# MCU.net
KiCad netlist of a schematic drawn in Altium Designer
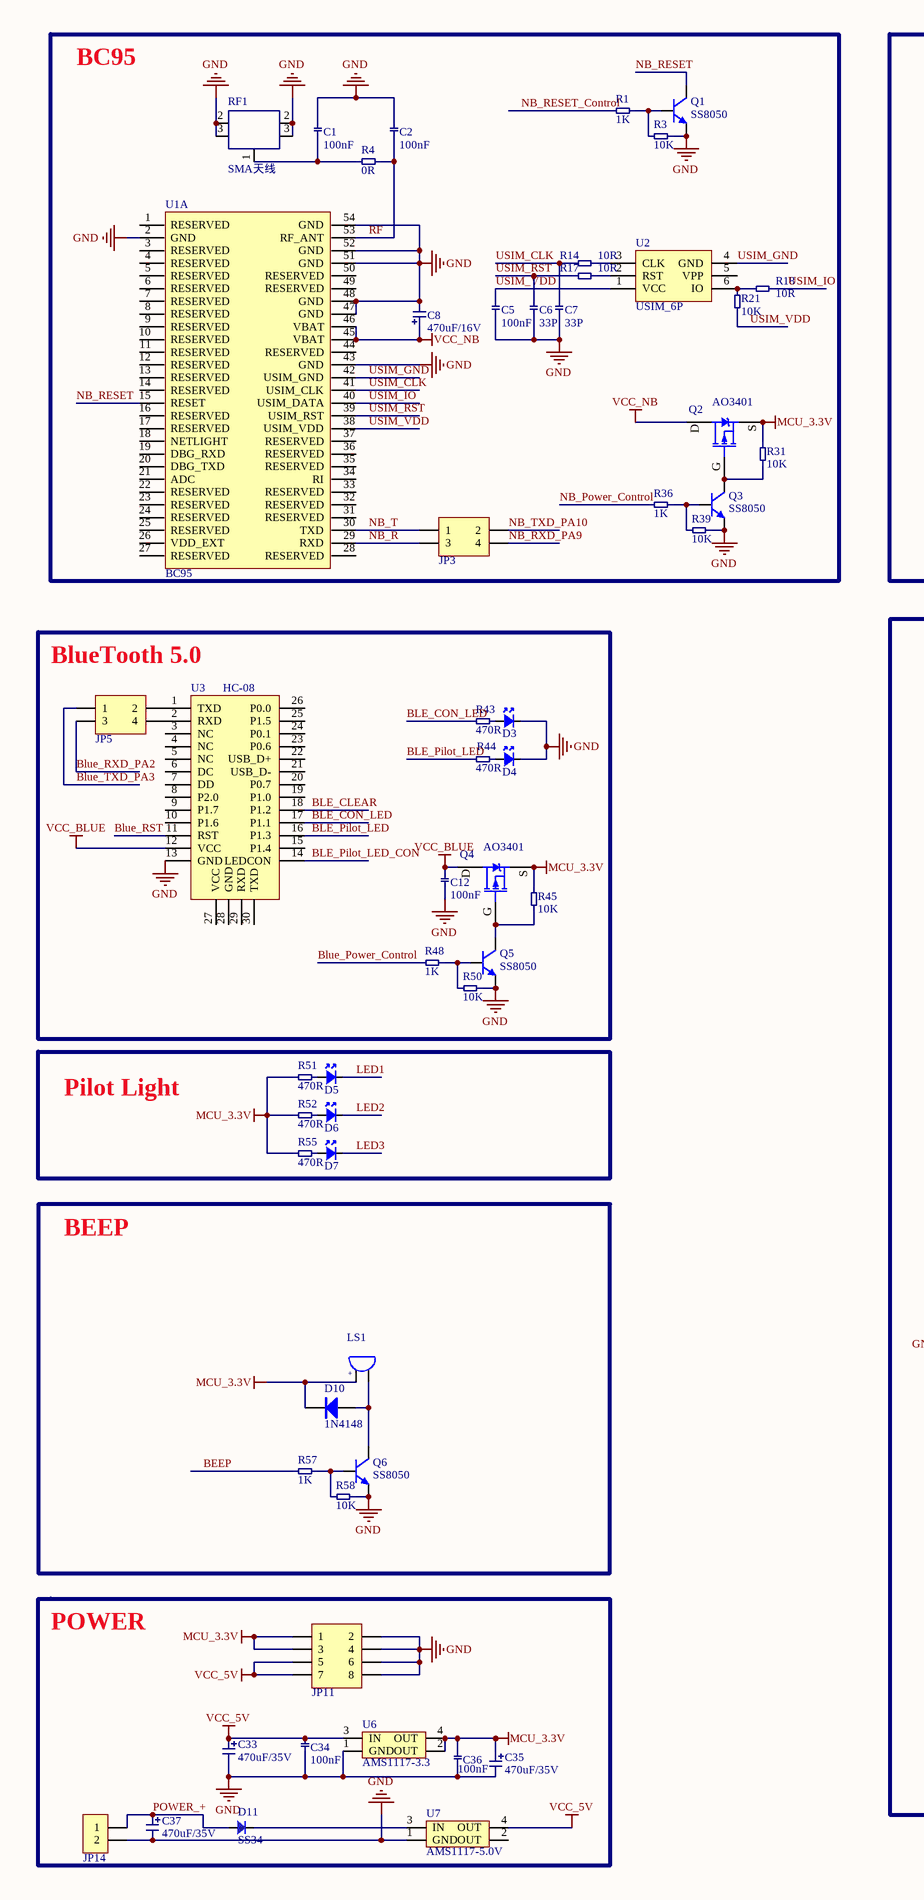
[diagram p0: MCU.SchDoc, left]
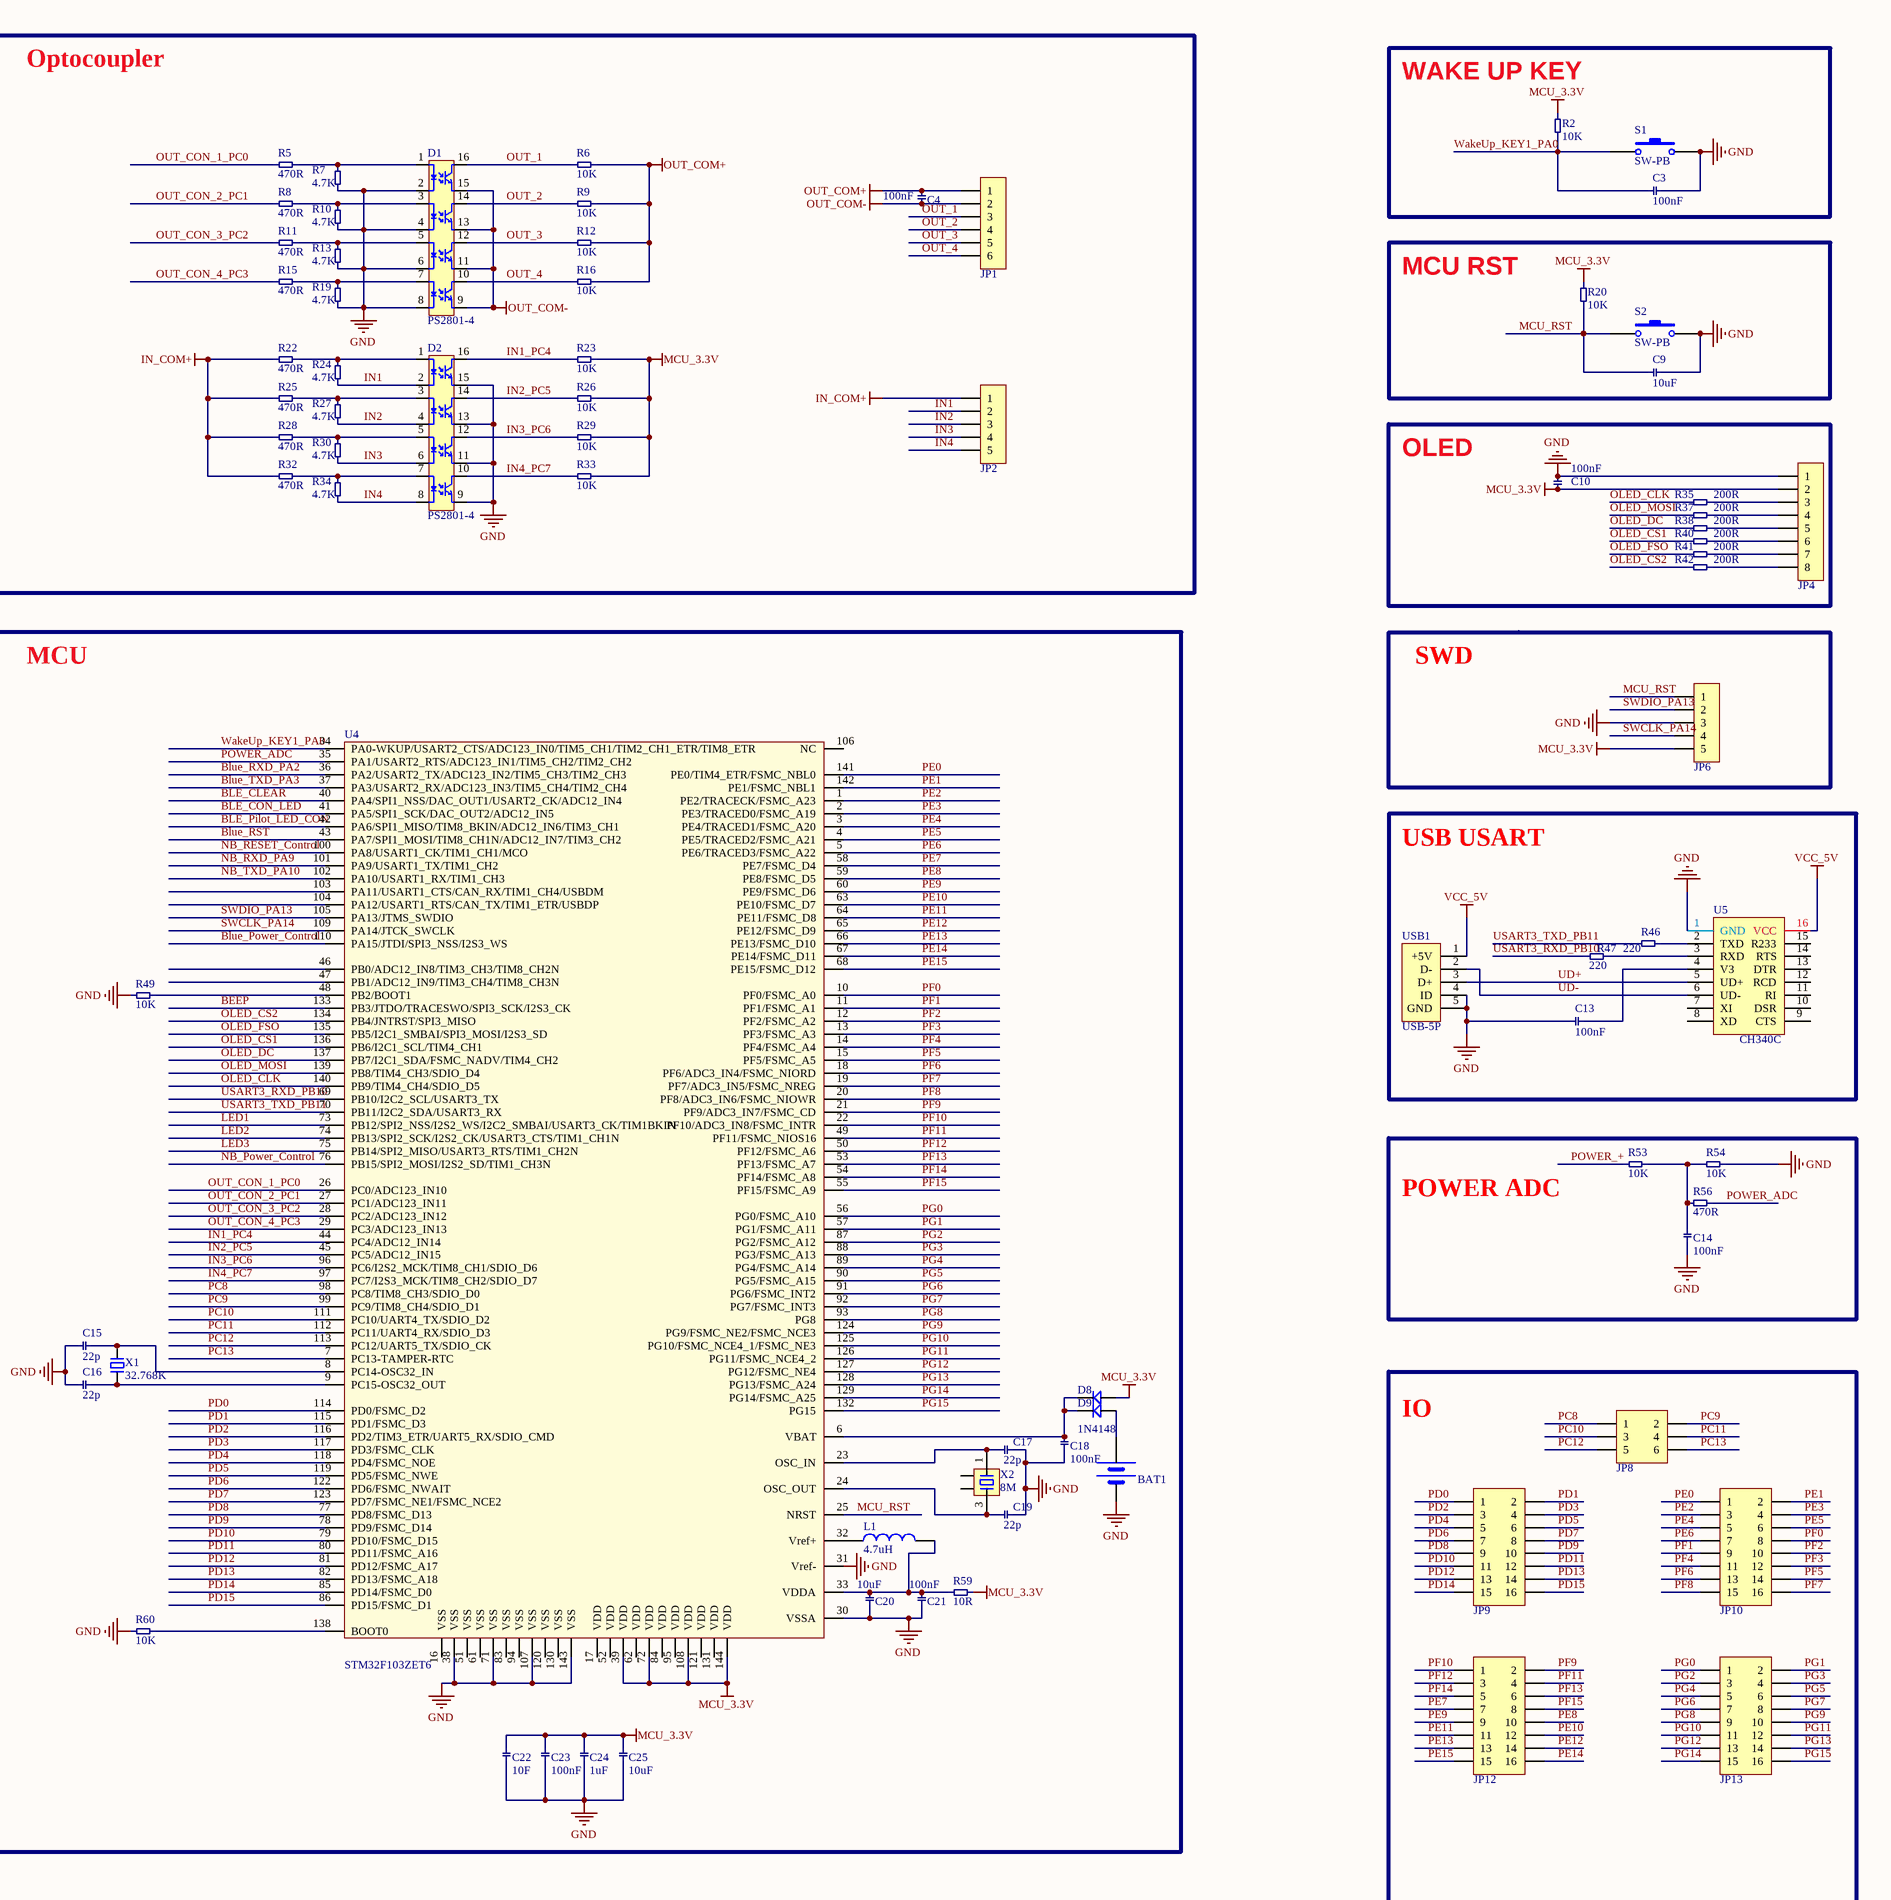
[diagram p1: MCU.SchDoc, right]

(export (version "E")
  (design (tool "Eeschema 10.0.6"))
  (components
    (comp (ref "BAT1")
      (value "BATT")
      (footprint "VBAT")
      (libsource (lib "WarShip V3 STM32103封装库") (part "BAT"))
    )
    (comp (ref "C1") (value "100nF") (footprint "0603CC") (libsource (lib "LFZ@WLP") (part "cap")))
    (comp (ref "C2") (value "100nF") (footprint "0603CC") (libsource (lib "LFZ@WLP") (part "cap")))
    (comp (ref "C3") (value "100nF") (footprint "0603CC") (libsource (lib "LFZ@WLP") (part "cap")))
    (comp (ref "C4") (value "100nF") (footprint "0603CC") (libsource (lib "LFZ@WLP") (part "cap")))
    (comp (ref "C5") (value "100nF") (footprint "0603CC") (libsource (lib "LFZ@WLP") (part "cap")))
    (comp (ref "C6") (value "33P") (footprint "0603CC") (libsource (lib "LFZ@WLP") (part "cap")))
    (comp (ref "C7") (value "33P") (footprint "0603CC") (libsource (lib "LFZ@WLP") (part "cap")))
    (comp (ref "C8") (value "470uF/16V") (footprint "C3216") (libsource (lib "LFZ@WLP") (part "Ecap")))
    (comp (ref "C9") (value "10uF") (footprint "0603CC") (libsource (lib "LFZ@WLP") (part "cap")))
    (comp (ref "C10") (value "100nF") (footprint "0603CC") (libsource (lib "LFZ@WLP") (part "cap")))
    (comp (ref "C12") (value "100nF") (footprint "0603CC") (libsource (lib "LFZ@WLP") (part "cap")))
    (comp (ref "C13") (value "100nF") (footprint "0603CC") (libsource (lib "LFZ@WLP") (part "cap")))
    (comp (ref "C14") (value "100nF") (footprint "0603CC") (libsource (lib "LFZ@WLP") (part "cap")))
    (comp (ref "C15") (value "22p") (footprint "0603CC") (libsource (lib "LFZ@WLP") (part "cap")))
    (comp (ref "C16") (value "22p") (footprint "0603CC") (libsource (lib "LFZ@WLP") (part "cap")))
    (comp (ref "C17") (value "22p") (footprint "0603CC") (libsource (lib "LFZ@WLP") (part "cap")))
    (comp (ref "C18") (value "100nF") (footprint "0603CC") (libsource (lib "LFZ@WLP") (part "cap")))
    (comp (ref "C19") (value "22p") (footprint "0603CC") (libsource (lib "LFZ@WLP") (part "cap")))
    (comp (ref "C20") (value "10uF") (footprint "0603CC") (libsource (lib "LFZ@WLP") (part "cap")))
    (comp (ref "C21") (value "100nF") (footprint "0603CC") (libsource (lib "LFZ@WLP") (part "cap")))
    (comp (ref "C22") (value "10F") (footprint "0603CC") (libsource (lib "LFZ@WLP") (part "cap")))
    (comp (ref "C23") (value "100nF") (footprint "0603CC") (libsource (lib "LFZ@WLP") (part "cap")))
    (comp (ref "C24") (value "1uF") (footprint "0603CC") (libsource (lib "LFZ@WLP") (part "cap")))
    (comp (ref "C25") (value "10uF") (footprint "0603CC") (libsource (lib "LFZ@WLP") (part "cap")))
    (comp (ref "C33") (value "470uF/35V") (footprint "CD A(3216)") (libsource (lib "LFZ@WLP") (part "Ecap")))
    (comp (ref "C34") (value "100nF") (footprint "0603CC") (libsource (lib "LFZ@WLP") (part "cap")))
    (comp (ref "C35") (value "470uF/35V") (footprint "C3216") (libsource (lib "LFZ@WLP") (part "Ecap")))
    (comp (ref "C36") (value "100nF") (footprint "0603CC") (libsource (lib "LFZ@WLP") (part "cap")))
    (comp (ref "C37") (value "470uF/35V") (footprint "CD A(3216)") (libsource (lib "LFZ@WLP") (part "Ecap")))
    (comp (ref "D1") (value "PS2801-4") (footprint "SOP16_N") (libsource (lib "LFZ@WLP") (part "PC847")))
    (comp (ref "D2") (value "PS2801-4") (footprint "SOP16_N") (libsource (lib "LFZ@WLP") (part "PC847")))
    (comp (ref "D3") (value "LED") (footprint "LED 0603G") (libsource (lib "LFZ@WLP") (part "LED")))
    (comp (ref "D4") (value "LED") (footprint "LED 0603R") (libsource (lib "LFZ@WLP") (part "LED")))
    (comp (ref "D5") (value "LED") (footprint "LED 3MM-G") (libsource (lib "LFZ@WLP") (part "LED")))
    (comp (ref "D6") (value "LED") (footprint "LED 3MM-B") (libsource (lib "LFZ@WLP") (part "LED")))
    (comp (ref "D7") (value "LED") (footprint "LED 3MM-R") (libsource (lib "LFZ@WLP") (part "LED")))
    (comp (ref "D8")
      (value "1N4148")
      (footprint "SOD-323")
      (libsource (lib "WarShip V3 STM32103封装库") (part "D"))
    )
    (comp (ref "D9")
      (value "1N4148")
      (footprint "SOD-323")
      (libsource (lib "WarShip V3 STM32103封装库") (part "D"))
    )
    (comp (ref "D10")
      (value "1N4148")
      (footprint "SOD-323")
      (description "高速开关二极管")
      (fields (field (name "版权归属") "源创客"))
      (libsource (lib "8.1   - 二极管-整流桥") (part "1N4148"))
    )
    (comp (ref "D11") (value "SS34") (footprint "SMA") (libsource (lib "Diod") (part "Diod")))
    (comp (ref "JP1")
      (value "HDR-1X6")
      (footprint "XH2.54-LI-6P")
      (description "6P接插件")
      (fields (field (name "版权归属") "源创客"))
      (libsource (lib "4.5   - 接插件-脚距2.54") (part "Header 6"))
    )
    (comp (ref "JP2")
      (value "HDR-1X5")
      (footprint "XH2.54-LI-5P")
      (description "5P接插件")
      (fields (field (name "版权归属") "源创客"))
      (libsource (lib "4.5   - 接插件-脚距2.54") (part "Header 5"))
    )
    (comp (ref "JP3")
      (value "Header2X2")
      (footprint "HDR2.54-LI-2x2P")
      (description "2*2P接插件")
      (fields (field (name "版权归属") "源创客"))
      (libsource (lib "4.5   - 接插件-脚距2.54") (part "Header 2X2"))
    )
    (comp (ref "JP4")
      (value "HDR-1X8")
      (footprint "HDR2.54-M-LI-8P")
      (description "8P接插件")
      (fields (field (name "版权归属") "源创客"))
      (libsource (lib "4.5   - 接插件-脚距2.54") (part "Header 8"))
    )
    (comp (ref "JP5")
      (value "Header2X2")
      (footprint "HDR2.54-LI-2x2P")
      (description "2*2P接插件")
      (fields (field (name "版权归属") "源创客"))
      (libsource (lib "4.5   - 接插件-脚距2.54") (part "Header 2X2"))
    )
    (comp (ref "JP6")
      (value "HDR-1X5")
      (footprint "HDR2.54-LI-5P")
      (description "5P接插件")
      (fields (field (name "版权归属") "源创客"))
      (libsource (lib "4.5   - 接插件-脚距2.54") (part "Header 5"))
    )
    (comp (ref "JP8")
      (value "Header3X2")
      (footprint "HDR2.54-LI-2x3P")
      (description "3*2P接插件")
      (fields (field (name "版权归属") "源创客"))
      (libsource (lib "4.5   - 接插件-脚距2.54") (part "Header 3X2"))
    )
    (comp (ref "JP9")
      (value "Header 8X2")
      (footprint "HDR2.54-LI-2x8P")
      (description "8*2P接插件")
      (fields (field (name "版权归属") "源创客"))
      (libsource (lib "4.5   - 接插件-脚距2.54") (part "Header 8X2"))
    )
    (comp (ref "JP10")
      (value "Header 8X2")
      (footprint "HDR2.54-LI-2x8P")
      (description "8*2P接插件")
      (fields (field (name "版权归属") "源创客"))
      (libsource (lib "4.5   - 接插件-脚距2.54") (part "Header 8X2"))
    )
    (comp (ref "JP11")
      (value "Header 4X2")
      (footprint "HDR2.54-LI-2x4P")
      (description "4*2P接插件")
      (fields (field (name "版权归属") "源创客"))
      (libsource (lib "4.5   - 接插件-脚距2.54") (part "Header 4X2"))
    )
    (comp (ref "JP12")
      (value "Header 8X2")
      (footprint "HDR2.54-LI-2x8P")
      (description "8*2P接插件")
      (fields (field (name "版权归属") "源创客"))
      (libsource (lib "4.5   - 接插件-脚距2.54") (part "Header 8X2"))
    )
    (comp (ref "JP13")
      (value "Header 8X2")
      (footprint "HDR2.54-LI-2x8P")
      (description "8*2P接插件")
      (fields (field (name "版权归属") "源创客"))
      (libsource (lib "4.5   - 接插件-脚距2.54") (part "Header 8X2"))
    )
    (comp (ref "JP14")
      (value "HDR-1X2")
      (footprint "XH2.54-LI-2P")
      (description "2P接插件")
      (fields (field (name "版权归属") "源创客"))
      (libsource (lib "4.5   - 接插件-脚距2.54") (part "Header 2"))
    )
    (comp (ref "L1")
      (value "4.7uH")
      (footprint "L 0603")
      (description "小功率贴片电感")
      (fields (field (name "版权归属") "源创客"))
      (libsource (lib "3.1   - 电阻-电容-电感") (part "L"))
    )
    (comp (ref "LS1")
      (value "DC5V")
      (footprint "BEEP 5x9x5.5")
      (description "蜂鸣器")
      (fields (field (name "版权归属") "源创客"))
      (libsource (lib "15.1 - 未分类器件") (part "BEEP"))
    )
    (comp (ref "Q1")
      (value "SS8050")
      (footprint "SOT23-3N")
      (description "高频放大-NPN型")
      (fields (field (name "版权归属") "源创客"))
      (libsource (lib "6.2   - 三极管") (part "8050-SMD"))
    )
    (comp (ref "Q2")
      (value "AO3401")
      (footprint "SOT23-3N")
      (description "P沟道场效应管")
      (fields (field (name "版权归属") "源创客"))
      (libsource (lib "6.1   - 场效应管-可控硅") (part "SI2301"))
    )
    (comp (ref "Q3")
      (value "SS8050")
      (footprint "SOT23-3N")
      (description "高频放大-NPN型")
      (fields (field (name "版权归属") "源创客"))
      (libsource (lib "6.2   - 三极管") (part "8050-SMD"))
    )
    (comp (ref "Q4")
      (value "AO3401")
      (footprint "SOT23-3N")
      (description "P沟道场效应管")
      (fields (field (name "版权归属") "源创客"))
      (libsource (lib "6.1   - 场效应管-可控硅") (part "SI2301"))
    )
    (comp (ref "Q5")
      (value "SS8050")
      (footprint "SOT23-3N")
      (description "高频放大-NPN型")
      (fields (field (name "版权归属") "源创客"))
      (libsource (lib "6.2   - 三极管") (part "8050-SMD"))
    )
    (comp (ref "Q6")
      (value "SS8050")
      (footprint "SOT23-3N")
      (description "高频放大-NPN型")
      (fields (field (name "版权归属") "源创客"))
      (libsource (lib "6.2   - 三极管") (part "8050-SMD"))
    )
    (comp (ref "R1") (value "1K") (footprint "0603RR") (libsource (lib "LFZ@WLP") (part "res")))
    (comp (ref "R2") (value "10K") (footprint "0603RR") (libsource (lib "LFZ@WLP") (part "res")))
    (comp (ref "R3") (value "10K") (footprint "0603RR") (libsource (lib "LFZ@WLP") (part "res")))
    (comp (ref "R4") (value "0R") (footprint "0603RR") (libsource (lib "LFZ@WLP") (part "res")))
    (comp (ref "R5") (value "470R") (footprint "0603RR") (libsource (lib "LFZ@WLP") (part "res")))
    (comp (ref "R6") (value "10K") (footprint "0603RR") (libsource (lib "LFZ@WLP") (part "res")))
    (comp (ref "R7") (value "4.7K") (footprint "0603RR") (libsource (lib "LFZ@WLP") (part "res")))
    (comp (ref "R8") (value "470R") (footprint "0603RR") (libsource (lib "LFZ@WLP") (part "res")))
    (comp (ref "R9") (value "10K") (footprint "0603RR") (libsource (lib "LFZ@WLP") (part "res")))
    (comp (ref "R10") (value "4.7K") (footprint "0603RR") (libsource (lib "LFZ@WLP") (part "res")))
    (comp (ref "R11") (value "470R") (footprint "0603RR") (libsource (lib "LFZ@WLP") (part "res")))
    (comp (ref "R12") (value "10K") (footprint "0603RR") (libsource (lib "LFZ@WLP") (part "res")))
    (comp (ref "R13") (value "4.7K") (footprint "0603RR") (libsource (lib "LFZ@WLP") (part "res")))
    (comp (ref "R14") (value "10R") (footprint "0603RR") (libsource (lib "LFZ@WLP") (part "res")))
    (comp (ref "R15") (value "470R") (footprint "0603RR") (libsource (lib "LFZ@WLP") (part "res")))
    (comp (ref "R16") (value "10K") (footprint "0603RR") (libsource (lib "LFZ@WLP") (part "res")))
    (comp (ref "R17") (value "10R") (footprint "0603RR") (libsource (lib "LFZ@WLP") (part "res")))
    (comp (ref "R18") (value "10R") (footprint "0603RR") (libsource (lib "LFZ@WLP") (part "res")))
    (comp (ref "R19") (value "4.7K") (footprint "0603RR") (libsource (lib "LFZ@WLP") (part "res")))
    (comp (ref "R20") (value "10K") (footprint "0603RR") (libsource (lib "LFZ@WLP") (part "res")))
    (comp (ref "R21") (value "10K") (footprint "0603RR") (libsource (lib "LFZ@WLP") (part "res")))
    (comp (ref "R22") (value "470R") (footprint "0603RR") (libsource (lib "LFZ@WLP") (part "res")))
    (comp (ref "R23") (value "10K") (footprint "0603RR") (libsource (lib "LFZ@WLP") (part "res")))
    (comp (ref "R24") (value "4.7K") (footprint "0603RR") (libsource (lib "LFZ@WLP") (part "res")))
    (comp (ref "R25") (value "470R") (footprint "0603RR") (libsource (lib "LFZ@WLP") (part "res")))
    (comp (ref "R26") (value "10K") (footprint "0603RR") (libsource (lib "LFZ@WLP") (part "res")))
    (comp (ref "R27") (value "4.7K") (footprint "0603RR") (libsource (lib "LFZ@WLP") (part "res")))
    (comp (ref "R28") (value "470R") (footprint "0603RR") (libsource (lib "LFZ@WLP") (part "res")))
    (comp (ref "R29") (value "10K") (footprint "0603RR") (libsource (lib "LFZ@WLP") (part "res")))
    (comp (ref "R30") (value "4.7K") (footprint "0603RR") (libsource (lib "LFZ@WLP") (part "res")))
    (comp (ref "R31") (value "10K") (footprint "0603RR") (libsource (lib "LFZ@WLP") (part "res")))
    (comp (ref "R32") (value "470R") (footprint "0603RR") (libsource (lib "LFZ@WLP") (part "res")))
    (comp (ref "R33") (value "10K") (footprint "0603RR") (libsource (lib "LFZ@WLP") (part "res")))
    (comp (ref "R34") (value "4.7K") (footprint "0603RR") (libsource (lib "LFZ@WLP") (part "res")))
    (comp (ref "R35") (value "200R") (footprint "0603RR") (libsource (lib "LFZ@WLP") (part "res")))
    (comp (ref "R36") (value "1K") (footprint "0603RR") (libsource (lib "LFZ@WLP") (part "res")))
    (comp (ref "R37") (value "200R") (footprint "0603RR") (libsource (lib "LFZ@WLP") (part "res")))
    (comp (ref "R38") (value "200R") (footprint "0603RR") (libsource (lib "LFZ@WLP") (part "res")))
    (comp (ref "R39") (value "10K") (footprint "0603RR") (libsource (lib "LFZ@WLP") (part "res")))
    (comp (ref "R40") (value "200R") (footprint "0603RR") (libsource (lib "LFZ@WLP") (part "res")))
    (comp (ref "R41") (value "200R") (footprint "0603RR") (libsource (lib "LFZ@WLP") (part "res")))
    (comp (ref "R42") (value "200R") (footprint "0603RR") (libsource (lib "LFZ@WLP") (part "res")))
    (comp (ref "R43") (value "470R") (footprint "0603RR") (libsource (lib "LFZ@WLP") (part "res")))
    (comp (ref "R44") (value "470R") (footprint "0603RR") (libsource (lib "LFZ@WLP") (part "res")))
    (comp (ref "R45") (value "10K") (footprint "0603RR") (libsource (lib "LFZ@WLP") (part "res")))
    (comp (ref "R46") (value "220") (footprint "0603RR") (libsource (lib "LFZ@WLP") (part "res")))
    (comp (ref "R47") (value "220") (footprint "0603RR") (libsource (lib "LFZ@WLP") (part "res")))
    (comp (ref "R48") (value "1K") (footprint "0603RR") (libsource (lib "LFZ@WLP") (part "res")))
    (comp (ref "R49") (value "10K") (footprint "0603RR") (libsource (lib "LFZ@WLP") (part "res")))
    (comp (ref "R50") (value "10K") (footprint "0603RR") (libsource (lib "LFZ@WLP") (part "res")))
    (comp (ref "R51") (value "470R") (footprint "0603RR") (libsource (lib "LFZ@WLP") (part "res")))
    (comp (ref "R52") (value "470R") (footprint "0603RR") (libsource (lib "LFZ@WLP") (part "res")))
    (comp (ref "R53") (value "10K") (footprint "0603RR") (libsource (lib "LFZ@WLP") (part "res")))
    (comp (ref "R54") (value "10K") (footprint "0603RR") (libsource (lib "LFZ@WLP") (part "res")))
    (comp (ref "R55") (value "470R") (footprint "0603RR") (libsource (lib "LFZ@WLP") (part "res")))
    (comp (ref "R56") (value "470R") (footprint "0603RR") (libsource (lib "LFZ@WLP") (part "res")))
    (comp (ref "R57") (value "1K") (footprint "0603RR") (libsource (lib "LFZ@WLP") (part "res")))
    (comp (ref "R58") (value "10K") (footprint "0603RR") (libsource (lib "LFZ@WLP") (part "res")))
    (comp (ref "R59") (value "10R") (footprint "0603RR") (libsource (lib "LFZ@WLP") (part "res")))
    (comp (ref "R60") (value "10K") (footprint "0603RR") (libsource (lib "LFZ@WLP") (part "res")))
    (comp (ref "RF1") (value "SMA天线") (libsource (lib "LFZ@WLP") (part "SMA天线")))
    (comp (ref "S1")
      (value "SW-PB")
      (footprint "TSW SMD-6*6*6")
      (description "Switch")
      (fields (field (name "PUBLISHER") "Altium Limited"))
      (libsource (lib "开关及电源") (part "SW-PB"))
    )
    (comp (ref "S2")
      (value "SW-PB")
      (footprint "TSW SMD-4*4*1.5")
      (description "Switch")
      (fields (field (name "PUBLISHER") "Altium Limited"))
      (libsource (lib "开关及电源") (part "SW-PB"))
    )
    (comp (ref "U1")
      (value "BC95")
      (footprint "BC95")
      (libsource (lib "Quectel_BC95_SCH_Part_Protel&AD_20170925") (part "BC95"))
    )
    (comp (ref "U2") (value "USIM_6P") (footprint "SIM 6P 自弹") (libsource (lib "XG-BM02") (part "USIM-6P")))
    (comp (ref "U3") (value "HC-08") (footprint "HC-08") (libsource (lib "LFZ@WLP") (part "HC-08")))
    (comp (ref "U4")
      (value "STM32F103ZET6")
      (footprint "LQFP144 20X20_L")
      (libsource (lib "WarShip V3 STM32103封装库") (part "STM32F103ZET6"))
    )
    (comp (ref "U5") (value "CH340C") (footprint "SOP16_L") (libsource (lib "LFZ@WLP") (part "CH340C")))
    (comp (ref "U6")
      (value "AMS1117-3.3")
      (footprint "SOT223_N")
      (libsource (lib "WarShip V3 STM32103封装库") (part "AMS1117"))
    )
    (comp (ref "U7")
      (value "AMS1117-5.0V")
      (footprint "SOT223_N")
      (libsource (lib "WarShip V3 STM32103封装库") (part "AMS1117"))
    )
    (comp (ref "USB1")
      (value "USB-5P")
      (footprint "USB-MICRO_A")
      (description "微型USB母座")
      (fields (field (name "版权归属") "源创客"))
      (libsource (lib "4.1   - 接口类") (part "USB-5P"))
    )
    (comp (ref "X1")
      (value "32.768K")
      (footprint "OSC 3215-2P")
      (description "2脚无源脚晶振")
      (fields (field (name "版权归属") "源创客"))
      (libsource (lib "10.1 - 保险丝-晶振") (part "XTAL-2P"))
    )
    (comp (ref "X2")
      (value "8M")
      (footprint "OSC 3225-4P")
      (description "4脚无源晶振")
      (fields (field (name "版权归属") "源创客"))
      (libsource (lib "10.1 - 保险丝-晶振") (part "XTAL-4P"))
    )
  )
  (nets
    (net (code "1") (name "/BEEP") (class "Default")
      (node (ref "R57") (pin "1") (pinfunction "1_1") (pintype "passive"))
      (node (ref "U4") (pin "133") (pinfunction "PB3/JTDO/TRACESWO/SPI3_SCK/I2S3_CK_133") (pintype "passive"))
    )
    (net (code "2") (name "/BLE_CLEAR") (class "Default")
      (node (ref "U3") (pin "18") (pinfunction "P1.2_18") (pintype "passive"))
      (node (ref "U4") (pin "40") (pinfunction "PA4/SPI1_NSS/DAC_OUT1/USART2_CK/ADC12_IN4_40") (pintype "passive"))
    )
    (net (code "3") (name "/BLE_CON_LED") (class "Default")
      (node (ref "R43") (pin "1") (pinfunction "1_1") (pintype "passive"))
      (node (ref "U3") (pin "17") (pinfunction "P1.1_17") (pintype "passive"))
      (node (ref "U4") (pin "41") (pinfunction "PA5/SPI1_SCK/DAC_OUT2/ADC12_IN5_41") (pintype "passive"))
    )
    (net (code "4") (name "/BLE_Pilot_LED") (class "Default")
      (node (ref "R44") (pin "1") (pinfunction "1_1") (pintype "passive"))
      (node (ref "U3") (pin "16") (pinfunction "P1.3_16") (pintype "passive"))
    )
    (net (code "5") (name "/BLE_Pilot_LED_CON") (class "Default")
      (node (ref "U3") (pin "14") (pinfunction "LEDCON_14") (pintype "passive"))
      (node (ref "U4") (pin "42") (pinfunction "PA6/SPI1_MISO/TIM8_BKIN/ADC12_IN6/TIM3_CH1_42") (pintype "passive"))
    )
    (net (code "6") (name "/Blue_Power_Control") (class "Default")
      (node (ref "R48") (pin "1") (pinfunction "1_1") (pintype "passive"))
      (node (ref "U4") (pin "110") (pinfunction "PA15/JTDI/SPI3_NSS/I2S3_WS_110") (pintype "passive"))
    )
    (net (code "7") (name "/Blue_RST") (class "Default")
      (node (ref "U3") (pin "11") (pinfunction "RST_11") (pintype "passive"))
      (node (ref "U4") (pin "43") (pinfunction "PA7/SPI1_MOSI/TIM8_CH1N/ADC12_IN7/TIM3_CH2_43") (pintype "passive"))
    )
    (net (code "8") (name "/Blue_RXD_PA2") (class "Default")
      (node (ref "JP5") (pin "3") (pinfunction "3_3") (pintype "passive"))
      (node (ref "U4") (pin "36") (pinfunction "PA2/USART2_TX/ADC123_IN2/TIM5_CH3/TIM2_CH3_36") (pintype "passive"))
    )
    (net (code "9") (name "/Blue_TXD_PA3") (class "Default")
      (node (ref "JP5") (pin "1") (pinfunction "1_1") (pintype "passive"))
      (node (ref "U4") (pin "37") (pinfunction "PA3/USART2_RX/ADC123_IN3/TIM5_CH4/TIM2_CH4_37") (pintype "passive"))
    )
    (net (code "10") (name "/IN1") (class "Default")
      (node (ref "D2") (pin "2") (pinfunction "IN_N_2") (pintype "passive"))
      (node (ref "JP2") (pin "2") (pinfunction "2_2") (pintype "passive"))
      (node (ref "R24") (pin "1") (pinfunction "1_1") (pintype "passive"))
    )
    (net (code "11") (name "/IN1_PC4") (class "Default")
      (node (ref "D2") (pin "16") (pinfunction "OUT_C_16") (pintype "passive"))
      (node (ref "R23") (pin "1") (pinfunction "1_1") (pintype "passive"))
      (node (ref "U4") (pin "44") (pinfunction "PC4/ADC12_IN14_44") (pintype "passive"))
    )
    (net (code "12") (name "/IN2") (class "Default")
      (node (ref "D2") (pin "4") (pinfunction "IN_N_4") (pintype "passive"))
      (node (ref "JP2") (pin "3") (pinfunction "3_3") (pintype "passive"))
      (node (ref "R27") (pin "1") (pinfunction "1_1") (pintype "passive"))
    )
    (net (code "13") (name "/IN2_PC5") (class "Default")
      (node (ref "D2") (pin "14") (pinfunction "OUT_C_14") (pintype "passive"))
      (node (ref "R26") (pin "1") (pinfunction "1_1") (pintype "passive"))
      (node (ref "U4") (pin "45") (pinfunction "PC5/ADC12_IN15_45") (pintype "passive"))
    )
    (net (code "14") (name "/IN3") (class "Default")
      (node (ref "D2") (pin "6") (pinfunction "IN_N_6") (pintype "passive"))
      (node (ref "JP2") (pin "4") (pinfunction "4_4") (pintype "passive"))
      (node (ref "R30") (pin "1") (pinfunction "1_1") (pintype "passive"))
    )
    (net (code "15") (name "/IN3_PC6") (class "Default")
      (node (ref "D2") (pin "12") (pinfunction "OUT_C_12") (pintype "passive"))
      (node (ref "R29") (pin "1") (pinfunction "1_1") (pintype "passive"))
      (node (ref "U4") (pin "96") (pinfunction "PC6/I2S2_MCK/TIM8_CH1/SDIO_D6_96") (pintype "passive"))
    )
    (net (code "16") (name "/IN4") (class "Default")
      (node (ref "D2") (pin "8") (pinfunction "IN_N_8") (pintype "passive"))
      (node (ref "JP2") (pin "5") (pinfunction "5_5") (pintype "passive"))
      (node (ref "R34") (pin "1") (pinfunction "1_1") (pintype "passive"))
    )
    (net (code "17") (name "/IN4_PC7") (class "Default")
      (node (ref "D2") (pin "10") (pinfunction "OUT_C_10") (pintype "passive"))
      (node (ref "R33") (pin "1") (pinfunction "1_1") (pintype "passive"))
      (node (ref "U4") (pin "97") (pinfunction "PC7/I2S3_MCK/TIM8_CH2/SDIO_D7_97") (pintype "passive"))
    )
    (net (code "18") (name "/LED1") (class "Default")
      (node (ref "D5") (pin "2") (pinfunction "CATHODE_2") (pintype "passive"))
      (node (ref "U4") (pin "73") (pinfunction "PB12/SPI2_NSS/I2S2_WS/I2C2_SMBAI/USART3_CK/TIM1BKIN_73") (pintype "passive"))
    )
    (net (code "19") (name "/LED2") (class "Default")
      (node (ref "D6") (pin "2") (pinfunction "CATHODE_2") (pintype "passive"))
      (node (ref "U4") (pin "74") (pinfunction "PB13/SPI2_SCK/I2S2_CK/USART3_CTS/TIM1_CH1N_74") (pintype "passive"))
    )
    (net (code "20") (name "/LED3") (class "Default")
      (node (ref "D7") (pin "2") (pinfunction "CATHODE_2") (pintype "passive"))
      (node (ref "U4") (pin "75") (pinfunction "PB14/SPI2_MISO/USART3_RTS/TIM1_CH2N_75") (pintype "passive"))
    )
    (net (code "21") (name "/MCU_RST") (class "Default")
      (node (ref "C9") (pin "2") (pinfunction "2_2") (pintype "passive"))
      (node (ref "JP6") (pin "1") (pinfunction "1_1") (pintype "passive"))
      (node (ref "R20") (pin "1") (pinfunction "1_1") (pintype "passive"))
      (node (ref "S2") (pin "1") (pinfunction "1_1") (pintype "passive"))
      (node (ref "U4") (pin "25") (pinfunction "NRST_25") (pintype "passive"))
    )
    (net (code "22") (name "/NB_Power_Control") (class "Default")
      (node (ref "R36") (pin "1") (pinfunction "1_1") (pintype "passive"))
      (node (ref "U4") (pin "76") (pinfunction "PB15/SPI2_MOSI/I2S2_SD/TIM1_CH3N_76") (pintype "passive"))
    )
    (net (code "23") (name "/NB_R") (class "Default")
      (node (ref "JP3") (pin "3") (pinfunction "3_3") (pintype "passive"))
      (node (ref "U1") (pin "29") (pinfunction "RXD_29") (pintype "passive"))
    )
    (net (code "24") (name "/NB_RESET") (class "Default")
      (node (ref "Q1") (pin "3") (pinfunction "C_3") (pintype "passive"))
      (node (ref "U1") (pin "15") (pinfunction "RESET_15") (pintype "passive"))
    )
    (net (code "25") (name "/NB_RESET_Control") (class "Default")
      (node (ref "R1") (pin "1") (pinfunction "1_1") (pintype "passive"))
      (node (ref "U4") (pin "100") (pinfunction "PA8/USART1_CK/TIM1_CH1/MCO_100") (pintype "passive"))
    )
    (net (code "26") (name "/NB_RXD_PA9") (class "Default")
      (node (ref "JP3") (pin "4") (pinfunction "4_4") (pintype "passive"))
      (node (ref "U4") (pin "101") (pinfunction "PA9/USART1_TX/TIM1_CH2_101") (pintype "passive"))
    )
    (net (code "27") (name "/NB_T") (class "Default")
      (node (ref "JP3") (pin "1") (pinfunction "1_1") (pintype "passive"))
      (node (ref "U1") (pin "30") (pinfunction "TXD_30") (pintype "passive"))
    )
    (net (code "28") (name "/NB_TXD_PA10") (class "Default")
      (node (ref "JP3") (pin "2") (pinfunction "2_2") (pintype "passive"))
      (node (ref "U4") (pin "102") (pinfunction "PA10/USART1_RX/TIM1_CH3_102") (pintype "passive"))
    )
    (net (code "29") (name "/OLED_CLK") (class "Default")
      (node (ref "R35") (pin "1") (pinfunction "1_1") (pintype "passive"))
      (node (ref "U4") (pin "140") (pinfunction "PB9/TIM4_CH4/SDIO_D5_140") (pintype "passive"))
    )
    (net (code "30") (name "/OLED_CS1") (class "Default")
      (node (ref "R40") (pin "1") (pinfunction "1_1") (pintype "passive"))
      (node (ref "U4") (pin "136") (pinfunction "PB6/I2C1_SCL/TIM4_CH1_136") (pintype "passive"))
    )
    (net (code "31") (name "/OLED_CS2") (class "Default")
      (node (ref "R42") (pin "1") (pinfunction "1_1") (pintype "passive"))
      (node (ref "U4") (pin "134") (pinfunction "PB4/JNTRST/SPI3_MISO_134") (pintype "passive"))
    )
    (net (code "32") (name "/OLED_DC") (class "Default")
      (node (ref "R38") (pin "1") (pinfunction "1_1") (pintype "passive"))
      (node (ref "U4") (pin "137") (pinfunction "PB7/I2C1_SDA/FSMC_NADV/TIM4_CH2_137") (pintype "passive"))
    )
    (net (code "33") (name "/OLED_FSO") (class "Default")
      (node (ref "R41") (pin "1") (pinfunction "1_1") (pintype "passive"))
      (node (ref "U4") (pin "135") (pinfunction "PB5/I2C1_SMBAI/SPI3_MOSI/I2S3_SD_135") (pintype "passive"))
    )
    (net (code "34") (name "/OLED_MOSI") (class "Default")
      (node (ref "R37") (pin "1") (pinfunction "1_1") (pintype "passive"))
      (node (ref "U4") (pin "139") (pinfunction "PB8/TIM4_CH3/SDIO_D4_139") (pintype "passive"))
    )
    (net (code "35") (name "/OUT_1") (class "Default")
      (node (ref "D1") (pin "16") (pinfunction "OUT_C_16") (pintype "passive"))
      (node (ref "JP1") (pin "3") (pinfunction "3_3") (pintype "passive"))
      (node (ref "R6") (pin "2") (pinfunction "2_2") (pintype "passive"))
    )
    (net (code "36") (name "/OUT_2") (class "Default")
      (node (ref "D1") (pin "14") (pinfunction "OUT_C_14") (pintype "passive"))
      (node (ref "JP1") (pin "4") (pinfunction "4_4") (pintype "passive"))
      (node (ref "R9") (pin "2") (pinfunction "2_2") (pintype "passive"))
    )
    (net (code "37") (name "/OUT_3") (class "Default")
      (node (ref "D1") (pin "12") (pinfunction "OUT_C_12") (pintype "passive"))
      (node (ref "JP1") (pin "5") (pinfunction "5_5") (pintype "passive"))
      (node (ref "R12") (pin "2") (pinfunction "2_2") (pintype "passive"))
    )
    (net (code "38") (name "/OUT_4") (class "Default")
      (node (ref "D1") (pin "10") (pinfunction "OUT_C_10") (pintype "passive"))
      (node (ref "JP1") (pin "6") (pinfunction "6_6") (pintype "passive"))
      (node (ref "R16") (pin "2") (pinfunction "2_2") (pintype "passive"))
    )
    (net (code "39") (name "/OUT_CON_1_PC0") (class "Default")
      (node (ref "R5") (pin "1") (pinfunction "1_1") (pintype "passive"))
      (node (ref "U4") (pin "26") (pinfunction "PC0/ADC123_IN10_26") (pintype "passive"))
    )
    (net (code "40") (name "/OUT_CON_2_PC1") (class "Default")
      (node (ref "R8") (pin "1") (pinfunction "1_1") (pintype "passive"))
      (node (ref "U4") (pin "27") (pinfunction "PC1/ADC123_IN11_27") (pintype "passive"))
    )
    (net (code "41") (name "/OUT_CON_3_PC2") (class "Default")
      (node (ref "R11") (pin "1") (pinfunction "1_1") (pintype "passive"))
      (node (ref "U4") (pin "28") (pinfunction "PC2/ADC123_IN12_28") (pintype "passive"))
    )
    (net (code "42") (name "/OUT_CON_4_PC3") (class "Default")
      (node (ref "R15") (pin "1") (pinfunction "1_1") (pintype "passive"))
      (node (ref "U4") (pin "29") (pinfunction "PC3/ADC123_IN13_29") (pintype "passive"))
    )
    (net (code "43") (name "/PC8") (class "Default")
      (node (ref "JP8") (pin "1") (pinfunction "1_1") (pintype "passive"))
      (node (ref "U4") (pin "98") (pinfunction "PC8/TIM8_CH3/SDIO_D0_98") (pintype "passive"))
    )
    (net (code "44") (name "/PC9") (class "Default")
      (node (ref "JP8") (pin "2") (pinfunction "2_2") (pintype "passive"))
      (node (ref "U4") (pin "99") (pinfunction "PC9/TIM8_CH4/SDIO_D1_99") (pintype "passive"))
    )
    (net (code "45") (name "/PC10") (class "Default")
      (node (ref "JP8") (pin "3") (pinfunction "3_3") (pintype "passive"))
      (node (ref "U4") (pin "111") (pinfunction "PC10/UART4_TX/SDIO_D2_111") (pintype "passive"))
    )
    (net (code "46") (name "/PC11") (class "Default")
      (node (ref "JP8") (pin "4") (pinfunction "4_4") (pintype "passive"))
      (node (ref "U4") (pin "112") (pinfunction "PC11/UART4_RX/SDIO_D3_112") (pintype "passive"))
    )
    (net (code "47") (name "/PC12") (class "Default")
      (node (ref "JP8") (pin "5") (pinfunction "5_5") (pintype "passive"))
      (node (ref "U4") (pin "113") (pinfunction "PC12/UART5_TX/SDIO_CK_113") (pintype "passive"))
    )
    (net (code "48") (name "/PC13") (class "Default")
      (node (ref "JP8") (pin "6") (pinfunction "6_6") (pintype "passive"))
      (node (ref "U4") (pin "7") (pinfunction "PC13-TAMPER-RTC_7") (pintype "passive"))
    )
    (net (code "49") (name "/PD0") (class "Default")
      (node (ref "JP9") (pin "1") (pinfunction "1_1") (pintype "passive"))
      (node (ref "U4") (pin "114") (pinfunction "PD0/FSMC_D2_114") (pintype "passive"))
    )
    (net (code "50") (name "/PD1") (class "Default")
      (node (ref "JP9") (pin "2") (pinfunction "2_2") (pintype "passive"))
      (node (ref "U4") (pin "115") (pinfunction "PD1/FSMC_D3_115") (pintype "passive"))
    )
    (net (code "51") (name "/PD2") (class "Default")
      (node (ref "JP9") (pin "3") (pinfunction "3_3") (pintype "passive"))
      (node (ref "U4") (pin "116") (pinfunction "PD2/TIM3_ETR/UART5_RX/SDIO_CMD_116") (pintype "passive"))
    )
    (net (code "52") (name "/PD3") (class "Default")
      (node (ref "JP9") (pin "4") (pinfunction "4_4") (pintype "passive"))
      (node (ref "U4") (pin "117") (pinfunction "PD3/FSMC_CLK_117") (pintype "passive"))
    )
    (net (code "53") (name "/PD4") (class "Default")
      (node (ref "JP9") (pin "5") (pinfunction "5_5") (pintype "passive"))
      (node (ref "U4") (pin "118") (pinfunction "PD4/FSMC_NOE_118") (pintype "passive"))
    )
    (net (code "54") (name "/PD5") (class "Default")
      (node (ref "JP9") (pin "6") (pinfunction "6_6") (pintype "passive"))
      (node (ref "U4") (pin "119") (pinfunction "PD5/FSMC_NWE_119") (pintype "passive"))
    )
    (net (code "55") (name "/PD6") (class "Default")
      (node (ref "JP9") (pin "7") (pinfunction "7_7") (pintype "passive"))
      (node (ref "U4") (pin "122") (pinfunction "PD6/FSMC_NWAIT_122") (pintype "passive"))
    )
    (net (code "56") (name "/PD7") (class "Default")
      (node (ref "JP9") (pin "8") (pinfunction "8_8") (pintype "passive"))
      (node (ref "U4") (pin "123") (pinfunction "PD7/FSMC_NE1/FSMC_NCE2_123") (pintype "passive"))
    )
    (net (code "57") (name "/PD8") (class "Default")
      (node (ref "JP9") (pin "9") (pinfunction "9_9") (pintype "passive"))
      (node (ref "U4") (pin "77") (pinfunction "PD8/FSMC_D13_77") (pintype "passive"))
    )
    (net (code "58") (name "/PD9") (class "Default")
      (node (ref "JP9") (pin "10") (pinfunction "10_10") (pintype "passive"))
      (node (ref "U4") (pin "78") (pinfunction "PD9/FSMC_D14_78") (pintype "passive"))
    )
    (net (code "59") (name "/PD10") (class "Default")
      (node (ref "JP9") (pin "11") (pinfunction "11_11") (pintype "passive"))
      (node (ref "U4") (pin "79") (pinfunction "PD10/FSMC_D15_79") (pintype "passive"))
    )
    (net (code "60") (name "/PD11") (class "Default")
      (node (ref "JP9") (pin "12") (pinfunction "12_12") (pintype "passive"))
      (node (ref "U4") (pin "80") (pinfunction "PD11/FSMC_A16_80") (pintype "passive"))
    )
    (net (code "61") (name "/PD12") (class "Default")
      (node (ref "JP9") (pin "13") (pinfunction "13_13") (pintype "passive"))
      (node (ref "U4") (pin "81") (pinfunction "PD12/FSMC_A17_81") (pintype "passive"))
    )
    (net (code "62") (name "/PD13") (class "Default")
      (node (ref "JP9") (pin "14") (pinfunction "14_14") (pintype "passive"))
      (node (ref "U4") (pin "82") (pinfunction "PD13/FSMC_A18_82") (pintype "passive"))
    )
    (net (code "63") (name "/PD14") (class "Default")
      (node (ref "JP9") (pin "15") (pinfunction "15_15") (pintype "passive"))
      (node (ref "U4") (pin "85") (pinfunction "PD14/FSMC_D0_85") (pintype "passive"))
    )
    (net (code "64") (name "/PD15") (class "Default")
      (node (ref "JP9") (pin "16") (pinfunction "16_16") (pintype "passive"))
      (node (ref "U4") (pin "86") (pinfunction "PD15/FSMC_D1_86") (pintype "passive"))
    )
    (net (code "65") (name "/PE0") (class "Default")
      (node (ref "JP10") (pin "1") (pinfunction "1_1") (pintype "passive"))
      (node (ref "U4") (pin "141") (pinfunction "PE0/TIM4_ETR/FSMC_NBL0_141") (pintype "passive"))
    )
    (net (code "66") (name "/PE1") (class "Default")
      (node (ref "JP10") (pin "2") (pinfunction "2_2") (pintype "passive"))
      (node (ref "U4") (pin "142") (pinfunction "PE1/FSMC_NBL1_142") (pintype "passive"))
    )
    (net (code "67") (name "/PE2") (class "Default")
      (node (ref "JP10") (pin "3") (pinfunction "3_3") (pintype "passive"))
      (node (ref "U4") (pin "1") (pinfunction "PE2/TRACECK/FSMC_A23_1") (pintype "passive"))
    )
    (net (code "68") (name "/PE3") (class "Default")
      (node (ref "JP10") (pin "4") (pinfunction "4_4") (pintype "passive"))
      (node (ref "U4") (pin "2") (pinfunction "PE3/TRACED0/FSMC_A19_2") (pintype "passive"))
    )
    (net (code "69") (name "/PE4") (class "Default")
      (node (ref "JP10") (pin "5") (pinfunction "5_5") (pintype "passive"))
      (node (ref "U4") (pin "3") (pinfunction "PE4/TRACED1/FSMC_A20_3") (pintype "passive"))
    )
    (net (code "70") (name "/PE5") (class "Default")
      (node (ref "JP10") (pin "6") (pinfunction "6_6") (pintype "passive"))
      (node (ref "U4") (pin "4") (pinfunction "PE5/TRACED2/FSMC_A21_4") (pintype "passive"))
    )
    (net (code "71") (name "/PE6") (class "Default")
      (node (ref "JP10") (pin "7") (pinfunction "7_7") (pintype "passive"))
      (node (ref "U4") (pin "5") (pinfunction "PE6/TRACED3/FSMC_A22_5") (pintype "passive"))
    )
    (net (code "72") (name "/PE7") (class "Default")
      (node (ref "JP12") (pin "7") (pinfunction "7_7") (pintype "passive"))
      (node (ref "U4") (pin "58") (pinfunction "PE7/FSMC_D4_58") (pintype "passive"))
    )
    (net (code "73") (name "/PE8") (class "Default")
      (node (ref "JP12") (pin "10") (pinfunction "10_10") (pintype "passive"))
      (node (ref "U4") (pin "59") (pinfunction "PE8/FSMC_D5_59") (pintype "passive"))
    )
    (net (code "74") (name "/PE9") (class "Default")
      (node (ref "JP12") (pin "9") (pinfunction "9_9") (pintype "passive"))
      (node (ref "U4") (pin "60") (pinfunction "PE9/FSMC_D6_60") (pintype "passive"))
    )
    (net (code "75") (name "/PE10") (class "Default")
      (node (ref "JP12") (pin "12") (pinfunction "12_12") (pintype "passive"))
      (node (ref "U4") (pin "63") (pinfunction "PE10/FSMC_D7_63") (pintype "passive"))
    )
    (net (code "76") (name "/PE11") (class "Default")
      (node (ref "JP12") (pin "11") (pinfunction "11_11") (pintype "passive"))
      (node (ref "U4") (pin "64") (pinfunction "PE11/FSMC_D8_64") (pintype "passive"))
    )
    (net (code "77") (name "/PE12") (class "Default")
      (node (ref "JP12") (pin "14") (pinfunction "14_14") (pintype "passive"))
      (node (ref "U4") (pin "65") (pinfunction "PE12/FSMC_D9_65") (pintype "passive"))
    )
    (net (code "78") (name "/PE13") (class "Default")
      (node (ref "JP12") (pin "13") (pinfunction "13_13") (pintype "passive"))
      (node (ref "U4") (pin "66") (pinfunction "PE13/FSMC_D10_66") (pintype "passive"))
    )
    (net (code "79") (name "/PE14") (class "Default")
      (node (ref "JP12") (pin "16") (pinfunction "16_16") (pintype "passive"))
      (node (ref "U4") (pin "67") (pinfunction "PE14/FSMC_D11_67") (pintype "passive"))
    )
    (net (code "80") (name "/PE15") (class "Default")
      (node (ref "JP12") (pin "15") (pinfunction "15_15") (pintype "passive"))
      (node (ref "U4") (pin "68") (pinfunction "PE15/FSMC_D12_68") (pintype "passive"))
    )
    (net (code "81") (name "/PF0") (class "Default")
      (node (ref "JP10") (pin "8") (pinfunction "8_8") (pintype "passive"))
      (node (ref "U4") (pin "10") (pinfunction "PF0/FSMC_A0_10") (pintype "passive"))
    )
    (net (code "82") (name "/PF1") (class "Default")
      (node (ref "JP10") (pin "9") (pinfunction "9_9") (pintype "passive"))
      (node (ref "U4") (pin "11") (pinfunction "PF1/FSMC_A1_11") (pintype "passive"))
    )
    (net (code "83") (name "/PF2") (class "Default")
      (node (ref "JP10") (pin "10") (pinfunction "10_10") (pintype "passive"))
      (node (ref "U4") (pin "12") (pinfunction "PF2/FSMC_A2_12") (pintype "passive"))
    )
    (net (code "84") (name "/PF3") (class "Default")
      (node (ref "JP10") (pin "12") (pinfunction "12_12") (pintype "passive"))
      (node (ref "U4") (pin "13") (pinfunction "PF3/FSMC_A3_13") (pintype "passive"))
    )
    (net (code "85") (name "/PF4") (class "Default")
      (node (ref "JP10") (pin "11") (pinfunction "11_11") (pintype "passive"))
      (node (ref "U4") (pin "14") (pinfunction "PF4/FSMC_A4_14") (pintype "passive"))
    )
    (net (code "86") (name "/PF5") (class "Default")
      (node (ref "JP10") (pin "14") (pinfunction "14_14") (pintype "passive"))
      (node (ref "U4") (pin "15") (pinfunction "PF5/FSMC_A5_15") (pintype "passive"))
    )
    (net (code "87") (name "/PF6") (class "Default")
      (node (ref "JP10") (pin "13") (pinfunction "13_13") (pintype "passive"))
      (node (ref "U4") (pin "18") (pinfunction "PF6/ADC3_IN4/FSMC_NIORD_18") (pintype "passive"))
    )
    (net (code "88") (name "/PF7") (class "Default")
      (node (ref "JP10") (pin "16") (pinfunction "16_16") (pintype "passive"))
      (node (ref "U4") (pin "19") (pinfunction "PF7/ADC3_IN5/FSMC_NREG_19") (pintype "passive"))
    )
    (net (code "89") (name "/PF8") (class "Default")
      (node (ref "JP10") (pin "15") (pinfunction "15_15") (pintype "passive"))
      (node (ref "U4") (pin "20") (pinfunction "PF8/ADC3_IN6/FSMC_NIOWR_20") (pintype "passive"))
    )
    (net (code "90") (name "/PF9") (class "Default")
      (node (ref "JP12") (pin "2") (pinfunction "2_2") (pintype "passive"))
      (node (ref "U4") (pin "21") (pinfunction "PF9/ADC3_IN7/FSMC_CD_21") (pintype "passive"))
    )
    (net (code "91") (name "/PF10") (class "Default")
      (node (ref "JP12") (pin "1") (pinfunction "1_1") (pintype "passive"))
      (node (ref "U4") (pin "22") (pinfunction "PF10/ADC3_IN8/FSMC_INTR_22") (pintype "passive"))
    )
    (net (code "92") (name "/PF11") (class "Default")
      (node (ref "JP12") (pin "4") (pinfunction "4_4") (pintype "passive"))
      (node (ref "U4") (pin "49") (pinfunction "PF11/FSMC_NIOS16_49") (pintype "passive"))
    )
    (net (code "93") (name "/PF12") (class "Default")
      (node (ref "JP12") (pin "3") (pinfunction "3_3") (pintype "passive"))
      (node (ref "U4") (pin "50") (pinfunction "PF12/FSMC_A6_50") (pintype "passive"))
    )
    (net (code "94") (name "/PF13") (class "Default")
      (node (ref "JP12") (pin "6") (pinfunction "6_6") (pintype "passive"))
      (node (ref "U4") (pin "53") (pinfunction "PF13/FSMC_A7_53") (pintype "passive"))
    )
    (net (code "95") (name "/PF14") (class "Default")
      (node (ref "JP12") (pin "5") (pinfunction "5_5") (pintype "passive"))
      (node (ref "U4") (pin "54") (pinfunction "PF14/FSMC_A8_54") (pintype "passive"))
    )
    (net (code "96") (name "/PF15") (class "Default")
      (node (ref "JP12") (pin "8") (pinfunction "8_8") (pintype "passive"))
      (node (ref "U4") (pin "55") (pinfunction "PF15/FSMC_A9_55") (pintype "passive"))
    )
    (net (code "97") (name "/PG0") (class "Default")
      (node (ref "JP13") (pin "1") (pinfunction "1_1") (pintype "passive"))
      (node (ref "U4") (pin "56") (pinfunction "PG0/FSMC_A10_56") (pintype "passive"))
    )
    (net (code "98") (name "/PG1") (class "Default")
      (node (ref "JP13") (pin "2") (pinfunction "2_2") (pintype "passive"))
      (node (ref "U4") (pin "57") (pinfunction "PG1/FSMC_A11_57") (pintype "passive"))
    )
    (net (code "99") (name "/PG2") (class "Default")
      (node (ref "JP13") (pin "3") (pinfunction "3_3") (pintype "passive"))
      (node (ref "U4") (pin "87") (pinfunction "PG2/FSMC_A12_87") (pintype "passive"))
    )
    (net (code "100") (name "/PG3") (class "Default")
      (node (ref "JP13") (pin "4") (pinfunction "4_4") (pintype "passive"))
      (node (ref "U4") (pin "88") (pinfunction "PG3/FSMC_A13_88") (pintype "passive"))
    )
    (net (code "101") (name "/PG4") (class "Default")
      (node (ref "JP13") (pin "5") (pinfunction "5_5") (pintype "passive"))
      (node (ref "U4") (pin "89") (pinfunction "PG4/FSMC_A14_89") (pintype "passive"))
    )
    (net (code "102") (name "/PG5") (class "Default")
      (node (ref "JP13") (pin "6") (pinfunction "6_6") (pintype "passive"))
      (node (ref "U4") (pin "90") (pinfunction "PG5/FSMC_A15_90") (pintype "passive"))
    )
    (net (code "103") (name "/PG6") (class "Default")
      (node (ref "JP13") (pin "7") (pinfunction "7_7") (pintype "passive"))
      (node (ref "U4") (pin "91") (pinfunction "PG6/FSMC_INT2_91") (pintype "passive"))
    )
    (net (code "104") (name "/PG7") (class "Default")
      (node (ref "JP13") (pin "8") (pinfunction "8_8") (pintype "passive"))
      (node (ref "U4") (pin "92") (pinfunction "PG7/FSMC_INT3_92") (pintype "passive"))
    )
    (net (code "105") (name "/PG8") (class "Default")
      (node (ref "JP13") (pin "9") (pinfunction "9_9") (pintype "passive"))
      (node (ref "U4") (pin "93") (pinfunction "PG8_93") (pintype "passive"))
    )
    (net (code "106") (name "/PG9") (class "Default")
      (node (ref "JP13") (pin "10") (pinfunction "10_10") (pintype "passive"))
      (node (ref "U4") (pin "124") (pinfunction "PG9/FSMC_NE2/FSMC_NCE3_124") (pintype "passive"))
    )
    (net (code "107") (name "/PG10") (class "Default")
      (node (ref "JP13") (pin "11") (pinfunction "11_11") (pintype "passive"))
      (node (ref "U4") (pin "125") (pinfunction "PG10/FSMC_NCE4_1/FSMC_NE3_125") (pintype "passive"))
    )
    (net (code "108") (name "/PG11") (class "Default")
      (node (ref "JP13") (pin "12") (pinfunction "12_12") (pintype "passive"))
      (node (ref "U4") (pin "126") (pinfunction "PG11/FSMC_NCE4_2_126") (pintype "passive"))
    )
    (net (code "109") (name "/PG12") (class "Default")
      (node (ref "JP13") (pin "13") (pinfunction "13_13") (pintype "passive"))
      (node (ref "U4") (pin "127") (pinfunction "PG12/FSMC_NE4_127") (pintype "passive"))
    )
    (net (code "110") (name "/PG13") (class "Default")
      (node (ref "JP13") (pin "14") (pinfunction "14_14") (pintype "passive"))
      (node (ref "U4") (pin "128") (pinfunction "PG13/FSMC_A24_128") (pintype "passive"))
    )
    (net (code "111") (name "/PG14") (class "Default")
      (node (ref "JP13") (pin "15") (pinfunction "15_15") (pintype "passive"))
      (node (ref "U4") (pin "129") (pinfunction "PG14/FSMC_A25_129") (pintype "passive"))
    )
    (net (code "112") (name "/PG15") (class "Default")
      (node (ref "JP13") (pin "16") (pinfunction "16_16") (pintype "passive"))
      (node (ref "U4") (pin "132") (pinfunction "PG15_132") (pintype "passive"))
    )
    (net (code "113") (name "/POWER_+") (class "Default")
      (node (ref "C37") (pin "1") (pinfunction "1_1") (pintype "passive"))
      (node (ref "D11") (pin "1") (pinfunction "ANODE_1") (pintype "passive"))
      (node (ref "JP14") (pin "1") (pinfunction "1_1") (pintype "passive"))
      (node (ref "R53") (pin "1") (pinfunction "1_1") (pintype "passive"))
    )
    (net (code "114") (name "/POWER_ADC") (class "Default")
      (node (ref "R56") (pin "1") (pinfunction "1_1") (pintype "passive"))
      (node (ref "U4") (pin "35") (pinfunction "PA1/USART2_RTS/ADC123_IN1/TIM5_CH2/TIM2_CH2_35") (pintype "passive"))
    )
    (net (code "115") (name "/RF") (class "Default")
      (node (ref "C2") (pin "1") (pinfunction "1_1") (pintype "passive"))
      (node (ref "R4") (pin "1") (pinfunction "1_1") (pintype "passive"))
      (node (ref "U1") (pin "53") (pinfunction "RF_ANT_53") (pintype "passive"))
    )
    (net (code "116") (name "/SWCLK_PA14") (class "Default")
      (node (ref "JP6") (pin "4") (pinfunction "4_4") (pintype "passive"))
      (node (ref "U4") (pin "109") (pinfunction "PA14/JTCK_SWCLK_109") (pintype "passive"))
    )
    (net (code "117") (name "/SWDIO_PA13") (class "Default")
      (node (ref "JP6") (pin "2") (pinfunction "2_2") (pintype "passive"))
      (node (ref "U4") (pin "105") (pinfunction "PA13/JTMS_SWDIO_105") (pintype "passive"))
    )
    (net (code "118") (name "/UD+") (class "Default")
      (node (ref "U5") (pin "5") (pinfunction "UD+_5") (pintype "passive"))
      (node (ref "USB1") (pin "3") (pinfunction "D+_3") (pintype "passive"))
    )
    (net (code "119") (name "/UD-") (class "Default")
      (node (ref "U5") (pin "6") (pinfunction "UD-_6") (pintype "passive"))
      (node (ref "USB1") (pin "2") (pinfunction "D-_2") (pintype "passive"))
    )
    (net (code "120") (name "/USART3_RXD_PB10") (class "Default")
      (node (ref "R47") (pin "1") (pinfunction "1_1") (pintype "passive"))
      (node (ref "U4") (pin "69") (pinfunction "PB10/I2C2_SCL/USART3_TX_69") (pintype "passive"))
    )
    (net (code "121") (name "/USART3_TXD_PB11") (class "Default")
      (node (ref "R46") (pin "1") (pinfunction "1_1") (pintype "passive"))
      (node (ref "U4") (pin "70") (pinfunction "PB11/I2C2_SDA/USART3_RX_70") (pintype "passive"))
    )
    (net (code "122") (name "/USIM_CLK") (class "Default")
      (node (ref "C7") (pin "2") (pinfunction "2_2") (pintype "passive"))
      (node (ref "R14") (pin "1") (pinfunction "1_1") (pintype "passive"))
      (node (ref "U1") (pin "41") (pinfunction "USIM_CLK_41") (pintype "passive"))
    )
    (net (code "123") (name "/USIM_GND") (class "Default")
      (node (ref "U1") (pin "42") (pinfunction "USIM_GND_42") (pintype "passive"))
      (node (ref "U2") (pin "4") (pinfunction "GND_4") (pintype "passive"))
    )
    (net (code "124") (name "/USIM_IO") (class "Default")
      (node (ref "R18") (pin "1") (pinfunction "1_1") (pintype "passive"))
      (node (ref "U1") (pin "40") (pinfunction "USIM_DATA_40") (pintype "passive"))
    )
    (net (code "125") (name "/USIM_RST") (class "Default")
      (node (ref "C6") (pin "2") (pinfunction "2_2") (pintype "passive"))
      (node (ref "R17") (pin "1") (pinfunction "1_1") (pintype "passive"))
      (node (ref "U1") (pin "39") (pinfunction "USIM_RST_39") (pintype "passive"))
    )
    (net (code "126") (name "/USIM_VDD") (class "Default")
      (node (ref "C5") (pin "2") (pinfunction "2_2") (pintype "passive"))
      (node (ref "R21") (pin "1") (pinfunction "1_1") (pintype "passive"))
      (node (ref "U1") (pin "38") (pinfunction "USIM_VDD_38") (pintype "passive"))
      (node (ref "U2") (pin "1") (pinfunction "VCC_1") (pintype "passive"))
    )
    (net (code "127") (name "/WakeUp_KEY1_PA0") (class "Default")
      (node (ref "C3") (pin "1") (pinfunction "1_1") (pintype "passive"))
      (node (ref "R2") (pin "1") (pinfunction "1_1") (pintype "passive"))
      (node (ref "S1") (pin "1") (pinfunction "1_1") (pintype "passive"))
      (node (ref "U4") (pin "34") (pinfunction "PA0-WKUP/USART2_CTS/ADC123_IN0/TIM5_CH1/TIM2_CH1_ETR/TIM8_ETR_34") (pintype "passive"))
    )
    (net (code "128") (name "GND") (class "Default")
      (node (ref "BAT1") (pin "2") (pinfunction "GND_2") (pintype "passive"))
      (node (ref "C1") (pin "2") (pinfunction "2_2") (pintype "passive"))
      (node (ref "C10") (pin "2") (pinfunction "2_2") (pintype "passive"))
      (node (ref "C12") (pin "1") (pinfunction "1_1") (pintype "passive"))
      (node (ref "C13") (pin "2") (pinfunction "2_2") (pintype "passive"))
      (node (ref "C14") (pin "1") (pinfunction "1_1") (pintype "passive"))
      (node (ref "C15") (pin "2") (pinfunction "2_2") (pintype "passive"))
      (node (ref "C16") (pin "2") (pinfunction "2_2") (pintype "passive"))
      (node (ref "C17") (pin "1") (pinfunction "1_1") (pintype "passive"))
      (node (ref "C18") (pin "1") (pinfunction "1_1") (pintype "passive"))
      (node (ref "C19") (pin "1") (pinfunction "1_1") (pintype "passive"))
      (node (ref "C2") (pin "2") (pinfunction "2_2") (pintype "passive"))
      (node (ref "C20") (pin "1") (pinfunction "1_1") (pintype "passive"))
      (node (ref "C21") (pin "1") (pinfunction "1_1") (pintype "passive"))
      (node (ref "C22") (pin "1") (pinfunction "1_1") (pintype "passive"))
      (node (ref "C23") (pin "1") (pinfunction "1_1") (pintype "passive"))
      (node (ref "C24") (pin "1") (pinfunction "1_1") (pintype "passive"))
      (node (ref "C25") (pin "1") (pinfunction "1_1") (pintype "passive"))
      (node (ref "C3") (pin "2") (pinfunction "2_2") (pintype "passive"))
      (node (ref "C33") (pin "2") (pinfunction "2_2") (pintype "passive"))
      (node (ref "C34") (pin "1") (pinfunction "1_1") (pintype "passive"))
      (node (ref "C35") (pin "2") (pinfunction "2_2") (pintype "passive"))
      (node (ref "C36") (pin "1") (pinfunction "1_1") (pintype "passive"))
      (node (ref "C37") (pin "2") (pinfunction "2_2") (pintype "passive"))
      (node (ref "C5") (pin "1") (pinfunction "1_1") (pintype "passive"))
      (node (ref "C6") (pin "1") (pinfunction "1_1") (pintype "passive"))
      (node (ref "C7") (pin "1") (pinfunction "1_1") (pintype "passive"))
      (node (ref "C8") (pin "2") (pinfunction "2_2") (pintype "passive"))
      (node (ref "C9") (pin "1") (pinfunction "1_1") (pintype "passive"))
      (node (ref "D1") (pin "2") (pinfunction "IN_N_2") (pintype "passive"))
      (node (ref "D1") (pin "4") (pinfunction "IN_N_4") (pintype "passive"))
      (node (ref "D1") (pin "6") (pinfunction "IN_N_6") (pintype "passive"))
      (node (ref "D1") (pin "8") (pinfunction "IN_N_8") (pintype "passive"))
      (node (ref "D2") (pin "11") (pinfunction "OUT_E_11") (pintype "passive"))
      (node (ref "D2") (pin "13") (pinfunction "OUT_E_13") (pintype "passive"))
      (node (ref "D2") (pin "15") (pinfunction "OUT_E_15") (pintype "passive"))
      (node (ref "D2") (pin "9") (pinfunction "OUT_E_9") (pintype "passive"))
      (node (ref "D3") (pin "2") (pinfunction "CATHODE_2") (pintype "passive"))
      (node (ref "D4") (pin "2") (pinfunction "CATHODE_2") (pintype "passive"))
      (node (ref "JP11") (pin "2") (pinfunction "2_2") (pintype "passive"))
      (node (ref "JP11") (pin "4") (pinfunction "4_4") (pintype "passive"))
      (node (ref "JP11") (pin "6") (pinfunction "6_6") (pintype "passive"))
      (node (ref "JP11") (pin "8") (pinfunction "8_8") (pintype "passive"))
      (node (ref "JP14") (pin "2") (pinfunction "2_2") (pintype "passive"))
      (node (ref "JP4") (pin "1") (pinfunction "1_1") (pintype "passive"))
      (node (ref "JP6") (pin "3") (pinfunction "3_3") (pintype "passive"))
      (node (ref "Q1") (pin "2") (pinfunction "E_2") (pintype "passive"))
      (node (ref "Q3") (pin "2") (pinfunction "E_2") (pintype "passive"))
      (node (ref "Q5") (pin "2") (pinfunction "E_2") (pintype "passive"))
      (node (ref "Q6") (pin "2") (pinfunction "E_2") (pintype "passive"))
      (node (ref "R10") (pin "1") (pinfunction "1_1") (pintype "passive"))
      (node (ref "R13") (pin "1") (pinfunction "1_1") (pintype "passive"))
      (node (ref "R19") (pin "1") (pinfunction "1_1") (pintype "passive"))
      (node (ref "R3") (pin "2") (pinfunction "2_2") (pintype "passive"))
      (node (ref "R39") (pin "2") (pinfunction "2_2") (pintype "passive"))
      (node (ref "R49") (pin "1") (pinfunction "1_1") (pintype "passive"))
      (node (ref "R50") (pin "2") (pinfunction "2_2") (pintype "passive"))
      (node (ref "R54") (pin "2") (pinfunction "2_2") (pintype "passive"))
      (node (ref "R58") (pin "2") (pinfunction "2_2") (pintype "passive"))
      (node (ref "R60") (pin "1") (pinfunction "1_1") (pintype "passive"))
      (node (ref "R7") (pin "1") (pinfunction "1_1") (pintype "passive"))
      (node (ref "RF1") (pin "2") (pinfunction "2_2") (pintype "passive"))
      (node (ref "RF1") (pin "3") (pinfunction "3_3") (pintype "passive"))
      (node (ref "S1") (pin "2") (pinfunction "2_2") (pintype "passive"))
      (node (ref "S2") (pin "2") (pinfunction "2_2") (pintype "passive"))
      (node (ref "U1") (pin "2") (pinfunction "GND_2") (pintype "passive"))
      (node (ref "U1") (pin "43") (pinfunction "GND_43") (pintype "passive"))
      (node (ref "U1") (pin "47") (pinfunction "GND_47") (pintype "passive"))
      (node (ref "U1") (pin "48") (pinfunction "GND_48") (pintype "passive"))
      (node (ref "U1") (pin "51") (pinfunction "GND_51") (pintype "passive"))
      (node (ref "U1") (pin "52") (pinfunction "GND_52") (pintype "passive"))
      (node (ref "U1") (pin "54") (pinfunction "GND_54") (pintype "passive"))
      (node (ref "U3") (pin "13") (pinfunction "GND_13") (pintype "passive"))
      (node (ref "U4") (pin "107") (pinfunction "VSS_107") (pintype "passive"))
      (node (ref "U4") (pin "143") (pinfunction "VSS_143") (pintype "passive"))
      (node (ref "U4") (pin "30") (pinfunction "VSSA_30") (pintype "passive"))
      (node (ref "U4") (pin "31") (pinfunction "Vref-_31") (pintype "passive"))
      (node (ref "U4") (pin "38") (pinfunction "VSS_38") (pintype "passive"))
      (node (ref "U4") (pin "71") (pinfunction "VSS_71") (pintype "passive"))
      (node (ref "U5") (pin "1") (pinfunction "GND_1") (pintype "passive"))
      (node (ref "U6") (pin "1") (pinfunction "GND_1") (pintype "passive"))
      (node (ref "U7") (pin "1") (pinfunction "GND_1") (pintype "passive"))
      (node (ref "USB1") (pin "4") (pinfunction "ID_4") (pintype "passive"))
      (node (ref "USB1") (pin "5") (pinfunction "GND_5") (pintype "passive"))
    )
    (net (code "129") (name "IN_COM+") (class "Default")
      (node (ref "JP2") (pin "1") (pinfunction "1_1") (pintype "passive"))
      (node (ref "R22") (pin "1") (pinfunction "1_1") (pintype "passive"))
      (node (ref "R25") (pin "1") (pinfunction "1_1") (pintype "passive"))
      (node (ref "R28") (pin "1") (pinfunction "1_1") (pintype "passive"))
      (node (ref "R32") (pin "1") (pinfunction "1_1") (pintype "passive"))
    )
    (net (code "130") (name "MCU_3.3V") (class "Default")
      (node (ref "C10") (pin "1") (pinfunction "1_1") (pintype "passive"))
      (node (ref "C22") (pin "2") (pinfunction "2_2") (pintype "passive"))
      (node (ref "C23") (pin "2") (pinfunction "2_2") (pintype "passive"))
      (node (ref "C24") (pin "2") (pinfunction "2_2") (pintype "passive"))
      (node (ref "C25") (pin "2") (pinfunction "2_2") (pintype "passive"))
      (node (ref "C35") (pin "1") (pinfunction "1_1") (pintype "passive"))
      (node (ref "C36") (pin "2") (pinfunction "2_2") (pintype "passive"))
      (node (ref "D10") (pin "2") (pinfunction "K_2") (pintype "passive"))
      (node (ref "D8") (pin "1") (pintype "passive"))
      (node (ref "JP11") (pin "1") (pinfunction "1_1") (pintype "passive"))
      (node (ref "JP11") (pin "3") (pinfunction "3_3") (pintype "passive"))
      (node (ref "JP4") (pin "2") (pinfunction "2_2") (pintype "passive"))
      (node (ref "JP6") (pin "5") (pinfunction "5_5") (pintype "passive"))
      (node (ref "LS1") (pin "1") (pinfunction "1_1") (pintype "passive"))
      (node (ref "Q2") (pin "2") (pinfunction "S_2") (pintype "passive"))
      (node (ref "Q4") (pin "2") (pinfunction "S_2") (pintype "passive"))
      (node (ref "R2") (pin "2") (pinfunction "2_2") (pintype "passive"))
      (node (ref "R20") (pin "2") (pinfunction "2_2") (pintype "passive"))
      (node (ref "R23") (pin "2") (pinfunction "2_2") (pintype "passive"))
      (node (ref "R26") (pin "2") (pinfunction "2_2") (pintype "passive"))
      (node (ref "R29") (pin "2") (pinfunction "2_2") (pintype "passive"))
      (node (ref "R31") (pin "2") (pinfunction "2_2") (pintype "passive"))
      (node (ref "R33") (pin "2") (pinfunction "2_2") (pintype "passive"))
      (node (ref "R45") (pin "2") (pinfunction "2_2") (pintype "passive"))
      (node (ref "R51") (pin "1") (pinfunction "1_1") (pintype "passive"))
      (node (ref "R52") (pin "1") (pinfunction "1_1") (pintype "passive"))
      (node (ref "R55") (pin "1") (pinfunction "1_1") (pintype "passive"))
      (node (ref "R59") (pin "2") (pinfunction "2_2") (pintype "passive"))
      (node (ref "U4") (pin "108") (pinfunction "VDD_108") (pintype "passive"))
      (node (ref "U4") (pin "144") (pinfunction "VDD_144") (pintype "passive"))
      (node (ref "U4") (pin "39") (pinfunction "VDD_39") (pintype "passive"))
      (node (ref "U4") (pin "72") (pinfunction "VDD_72") (pintype "passive"))
      (node (ref "U6") (pin "2") (pinfunction "OUT_2") (pintype "passive"))
      (node (ref "U6") (pin "4") (pinfunction "OUT_4") (pintype "passive"))
    )
    (net (code "131") (name "Net-(BAT1-VCC)") (class "Default")
      (node (ref "BAT1") (pin "1") (pinfunction "VCC_1") (pintype "passive"))
      (node (ref "D9") (pin "1") (pintype "passive"))
    )
    (net (code "132") (name "Net-(C1-Pad1)") (class "Default")
      (node (ref "C1") (pin "1") (pinfunction "1_1") (pintype "passive"))
      (node (ref "R4") (pin "2") (pinfunction "2_2") (pintype "passive"))
      (node (ref "RF1") (pin "1") (pinfunction "1_1") (pintype "passive"))
    )
    (net (code "133") (name "Net-(C14-Pad2)") (class "Default")
      (node (ref "C14") (pin "2") (pinfunction "2_2") (pintype "passive"))
      (node (ref "R53") (pin "2") (pinfunction "2_2") (pintype "passive"))
      (node (ref "R54") (pin "1") (pinfunction "1_1") (pintype "passive"))
      (node (ref "R56") (pin "2") (pinfunction "2_2") (pintype "passive"))
    )
    (net (code "134") (name "Net-(D1-IN_P-Pad1)") (class "Default")
      (node (ref "D1") (pin "1") (pinfunction "IN_P_1") (pintype "passive"))
      (node (ref "R5") (pin "2") (pinfunction "2_2") (pintype "passive"))
      (node (ref "R7") (pin "2") (pinfunction "2_2") (pintype "passive"))
    )
    (net (code "135") (name "Net-(D1-IN_P-Pad3)") (class "Default")
      (node (ref "D1") (pin "3") (pinfunction "IN_P_3") (pintype "passive"))
      (node (ref "R10") (pin "2") (pinfunction "2_2") (pintype "passive"))
      (node (ref "R8") (pin "2") (pinfunction "2_2") (pintype "passive"))
    )
    (net (code "136") (name "Net-(D1-IN_P-Pad5)") (class "Default")
      (node (ref "D1") (pin "5") (pinfunction "IN_P_5") (pintype "passive"))
      (node (ref "R11") (pin "2") (pinfunction "2_2") (pintype "passive"))
      (node (ref "R13") (pin "2") (pinfunction "2_2") (pintype "passive"))
    )
    (net (code "137") (name "Net-(D1-IN_P-Pad7)") (class "Default")
      (node (ref "D1") (pin "7") (pinfunction "IN_P_7") (pintype "passive"))
      (node (ref "R15") (pin "2") (pinfunction "2_2") (pintype "passive"))
      (node (ref "R19") (pin "2") (pinfunction "2_2") (pintype "passive"))
    )
    (net (code "138") (name "Net-(D2-IN_P-Pad1)") (class "Default")
      (node (ref "D2") (pin "1") (pinfunction "IN_P_1") (pintype "passive"))
      (node (ref "R22") (pin "2") (pinfunction "2_2") (pintype "passive"))
      (node (ref "R24") (pin "2") (pinfunction "2_2") (pintype "passive"))
    )
    (net (code "139") (name "Net-(D2-IN_P-Pad3)") (class "Default")
      (node (ref "D2") (pin "3") (pinfunction "IN_P_3") (pintype "passive"))
      (node (ref "R25") (pin "2") (pinfunction "2_2") (pintype "passive"))
      (node (ref "R27") (pin "2") (pinfunction "2_2") (pintype "passive"))
    )
    (net (code "140") (name "Net-(D2-IN_P-Pad5)") (class "Default")
      (node (ref "D2") (pin "5") (pinfunction "IN_P_5") (pintype "passive"))
      (node (ref "R28") (pin "2") (pinfunction "2_2") (pintype "passive"))
      (node (ref "R30") (pin "2") (pinfunction "2_2") (pintype "passive"))
    )
    (net (code "141") (name "Net-(D2-IN_P-Pad7)") (class "Default")
      (node (ref "D2") (pin "7") (pinfunction "IN_P_7") (pintype "passive"))
      (node (ref "R32") (pin "2") (pinfunction "2_2") (pintype "passive"))
      (node (ref "R34") (pin "2") (pinfunction "2_2") (pintype "passive"))
    )
    (net (code "142") (name "Net-(D3-ANODE)") (class "Default")
      (node (ref "D3") (pin "1") (pinfunction "ANODE_1") (pintype "passive"))
      (node (ref "R43") (pin "2") (pinfunction "2_2") (pintype "passive"))
    )
    (net (code "143") (name "Net-(D4-ANODE)") (class "Default")
      (node (ref "D4") (pin "1") (pinfunction "ANODE_1") (pintype "passive"))
      (node (ref "R44") (pin "2") (pinfunction "2_2") (pintype "passive"))
    )
    (net (code "144") (name "Net-(D5-ANODE)") (class "Default")
      (node (ref "D5") (pin "1") (pinfunction "ANODE_1") (pintype "passive"))
      (node (ref "R51") (pin "2") (pinfunction "2_2") (pintype "passive"))
    )
    (net (code "145") (name "Net-(D6-ANODE)") (class "Default")
      (node (ref "D6") (pin "1") (pinfunction "ANODE_1") (pintype "passive"))
      (node (ref "R52") (pin "2") (pinfunction "2_2") (pintype "passive"))
    )
    (net (code "146") (name "Net-(D7-ANODE)") (class "Default")
      (node (ref "D7") (pin "1") (pinfunction "ANODE_1") (pintype "passive"))
      (node (ref "R55") (pin "2") (pinfunction "2_2") (pintype "passive"))
    )
    (net (code "147") (name "Net-(D10-A)") (class "Default")
      (node (ref "D10") (pin "1") (pinfunction "A_1") (pintype "passive"))
      (node (ref "LS1") (pin "2") (pinfunction "2_2") (pintype "passive"))
      (node (ref "Q6") (pin "3") (pinfunction "C_3") (pintype "passive"))
    )
    (net (code "148") (name "Net-(D11-CATHODE)") (class "Default")
      (node (ref "D11") (pin "2") (pinfunction "CATHODE_2") (pintype "passive"))
      (node (ref "U7") (pin "3") (pinfunction "IN_3") (pintype "passive"))
    )
    (net (code "149") (name "Net-(JP4-Pad3)") (class "Default")
      (node (ref "JP4") (pin "3") (pinfunction "3_3") (pintype "passive"))
      (node (ref "R35") (pin "2") (pinfunction "2_2") (pintype "passive"))
    )
    (net (code "150") (name "Net-(JP4-Pad4)") (class "Default")
      (node (ref "JP4") (pin "4") (pinfunction "4_4") (pintype "passive"))
      (node (ref "R37") (pin "2") (pinfunction "2_2") (pintype "passive"))
    )
    (net (code "151") (name "Net-(JP4-Pad5)") (class "Default")
      (node (ref "JP4") (pin "5") (pinfunction "5_5") (pintype "passive"))
      (node (ref "R38") (pin "2") (pinfunction "2_2") (pintype "passive"))
    )
    (net (code "152") (name "Net-(JP4-Pad6)") (class "Default")
      (node (ref "JP4") (pin "6") (pinfunction "6_6") (pintype "passive"))
      (node (ref "R40") (pin "2") (pinfunction "2_2") (pintype "passive"))
    )
    (net (code "153") (name "Net-(JP4-Pad7)") (class "Default")
      (node (ref "JP4") (pin "7") (pinfunction "7_7") (pintype "passive"))
      (node (ref "R41") (pin "2") (pinfunction "2_2") (pintype "passive"))
    )
    (net (code "154") (name "Net-(JP4-Pad8)") (class "Default")
      (node (ref "JP4") (pin "8") (pinfunction "8_8") (pintype "passive"))
      (node (ref "R42") (pin "2") (pinfunction "2_2") (pintype "passive"))
    )
    (net (code "155") (name "Net-(JP5-Pad2)") (class "Default")
      (node (ref "JP5") (pin "2") (pinfunction "2_2") (pintype "passive"))
      (node (ref "U3") (pin "1") (pinfunction "TXD_1") (pintype "passive"))
    )
    (net (code "156") (name "Net-(JP5-Pad4)") (class "Default")
      (node (ref "JP5") (pin "4") (pinfunction "4_4") (pintype "passive"))
      (node (ref "U3") (pin "2") (pinfunction "RXD_2") (pintype "passive"))
    )
    (net (code "157") (name "Net-(Q1-B)") (class "Default")
      (node (ref "Q1") (pin "1") (pinfunction "B_1") (pintype "passive"))
      (node (ref "R1") (pin "2") (pinfunction "2_2") (pintype "passive"))
      (node (ref "R3") (pin "1") (pinfunction "1_1") (pintype "passive"))
    )
    (net (code "158") (name "Net-(Q2-G)") (class "Default")
      (node (ref "Q2") (pin "1") (pinfunction "G_1") (pintype "passive"))
      (node (ref "Q3") (pin "3") (pinfunction "C_3") (pintype "passive"))
      (node (ref "R31") (pin "1") (pinfunction "1_1") (pintype "passive"))
    )
    (net (code "159") (name "Net-(Q3-B)") (class "Default")
      (node (ref "Q3") (pin "1") (pinfunction "B_1") (pintype "passive"))
      (node (ref "R36") (pin "2") (pinfunction "2_2") (pintype "passive"))
      (node (ref "R39") (pin "1") (pinfunction "1_1") (pintype "passive"))
    )
    (net (code "160") (name "Net-(Q4-G)") (class "Default")
      (node (ref "Q4") (pin "1") (pinfunction "G_1") (pintype "passive"))
      (node (ref "Q5") (pin "3") (pinfunction "C_3") (pintype "passive"))
      (node (ref "R45") (pin "1") (pinfunction "1_1") (pintype "passive"))
    )
    (net (code "161") (name "Net-(Q5-B)") (class "Default")
      (node (ref "Q5") (pin "1") (pinfunction "B_1") (pintype "passive"))
      (node (ref "R48") (pin "2") (pinfunction "2_2") (pintype "passive"))
      (node (ref "R50") (pin "1") (pinfunction "1_1") (pintype "passive"))
    )
    (net (code "162") (name "Net-(Q6-B)") (class "Default")
      (node (ref "Q6") (pin "1") (pinfunction "B_1") (pintype "passive"))
      (node (ref "R57") (pin "2") (pinfunction "2_2") (pintype "passive"))
      (node (ref "R58") (pin "1") (pinfunction "1_1") (pintype "passive"))
    )
    (net (code "163") (name "Net-(U2-CLK)") (class "Default")
      (node (ref "R14") (pin "2") (pinfunction "2_2") (pintype "passive"))
      (node (ref "U2") (pin "3") (pinfunction "CLK_3") (pintype "passive"))
    )
    (net (code "164") (name "Net-(U2-IO)") (class "Default")
      (node (ref "R18") (pin "2") (pinfunction "2_2") (pintype "passive"))
      (node (ref "R21") (pin "2") (pinfunction "2_2") (pintype "passive"))
      (node (ref "U2") (pin "6") (pinfunction "IO_6") (pintype "passive"))
    )
    (net (code "165") (name "Net-(U2-RST)") (class "Default")
      (node (ref "R17") (pin "2") (pinfunction "2_2") (pintype "passive"))
      (node (ref "U2") (pin "2") (pinfunction "RST_2") (pintype "passive"))
    )
    (net (code "166") (name "Net-(U4-BOOT0)") (class "Default")
      (node (ref "R60") (pin "2") (pinfunction "2_2") (pintype "passive"))
      (node (ref "U4") (pin "138") (pinfunction "BOOT0_138") (pintype "passive"))
    )
    (net (code "167") (name "Net-(U4-OSC_IN)") (class "Default")
      (node (ref "C17") (pin "2") (pinfunction "2_2") (pintype "passive"))
      (node (ref "U4") (pin "23") (pinfunction "OSC_IN_23") (pintype "passive"))
      (node (ref "X2") (pin "1") (pinfunction "1_1") (pintype "passive"))
    )
    (net (code "168") (name "Net-(U4-OSC_OUT)") (class "Default")
      (node (ref "C19") (pin "2") (pinfunction "2_2") (pintype "passive"))
      (node (ref "U4") (pin "24") (pinfunction "OSC_OUT_24") (pintype "passive"))
      (node (ref "X2") (pin "3") (pinfunction "3_3") (pintype "passive"))
    )
    (net (code "169") (name "Net-(U4-PB2{slash}BOOT1)") (class "Default")
      (node (ref "R49") (pin "2") (pinfunction "2_2") (pintype "passive"))
      (node (ref "U4") (pin "48") (pinfunction "PB2/BOOT1_48") (pintype "passive"))
    )
    (net (code "170") (name "Net-(U4-PC14-OSC32_IN)") (class "Default")
      (node (ref "C15") (pin "1") (pinfunction "1_1") (pintype "passive"))
      (node (ref "U4") (pin "8") (pinfunction "PC14-OSC32_IN_8") (pintype "passive"))
      (node (ref "X1") (pin "1") (pinfunction "1_1") (pintype "passive"))
    )
    (net (code "171") (name "Net-(U4-PC15-OSC32_OUT)") (class "Default")
      (node (ref "C16") (pin "1") (pinfunction "1_1") (pintype "passive"))
      (node (ref "U4") (pin "9") (pinfunction "PC15-OSC32_OUT_9") (pintype "passive"))
      (node (ref "X1") (pin "2") (pinfunction "2_2") (pintype "passive"))
    )
    (net (code "172") (name "Net-(U4-VBAT)") (class "Default")
      (node (ref "C18") (pin "2") (pinfunction "2_2") (pintype "passive"))
      (node (ref "D8") (pin "2") (pintype "passive"))
      (node (ref "D9") (pin "2") (pintype "passive"))
      (node (ref "U4") (pin "6") (pinfunction "VBAT_6") (pintype "passive"))
    )
    (net (code "173") (name "Net-(U4-VDDA)") (class "Default")
      (node (ref "C20") (pin "2") (pinfunction "2_2") (pintype "passive"))
      (node (ref "C21") (pin "2") (pinfunction "2_2") (pintype "passive"))
      (node (ref "L1") (pin "2") (pinfunction "2_2") (pintype "passive"))
      (node (ref "R59") (pin "1") (pinfunction "1_1") (pintype "passive"))
      (node (ref "U4") (pin "33") (pinfunction "VDDA_33") (pintype "passive"))
    )
    (net (code "174") (name "Net-(U4-Vref+)") (class "Default")
      (node (ref "L1") (pin "1") (pinfunction "1_1") (pintype "passive"))
      (node (ref "U4") (pin "32") (pinfunction "Vref+_32") (pintype "passive"))
    )
    (net (code "175") (name "Net-(U5-RXD)") (class "Default")
      (node (ref "R47") (pin "2") (pinfunction "2_2") (pintype "passive"))
      (node (ref "U5") (pin "3") (pinfunction "RXD_3") (pintype "passive"))
    )
    (net (code "176") (name "Net-(U5-TXD)") (class "Default")
      (node (ref "R46") (pin "2") (pinfunction "2_2") (pintype "passive"))
      (node (ref "U5") (pin "2") (pinfunction "TXD_2") (pintype "passive"))
    )
    (net (code "177") (name "Net-(U5-V3)") (class "Default")
      (node (ref "C13") (pin "1") (pinfunction "1_1") (pintype "passive"))
      (node (ref "U5") (pin "4") (pinfunction "V3_4") (pintype "passive"))
    )
    (net (code "178") (name "OUT_COM+") (class "Default")
      (node (ref "C4") (pin "2") (pinfunction "2_2") (pintype "passive"))
      (node (ref "JP1") (pin "1") (pinfunction "1_1") (pintype "passive"))
      (node (ref "R12") (pin "1") (pinfunction "1_1") (pintype "passive"))
      (node (ref "R16") (pin "1") (pinfunction "1_1") (pintype "passive"))
      (node (ref "R6") (pin "1") (pinfunction "1_1") (pintype "passive"))
      (node (ref "R9") (pin "1") (pinfunction "1_1") (pintype "passive"))
    )
    (net (code "179") (name "OUT_COM-") (class "Default")
      (node (ref "C4") (pin "1") (pinfunction "1_1") (pintype "passive"))
      (node (ref "D1") (pin "11") (pinfunction "OUT_E_11") (pintype "passive"))
      (node (ref "D1") (pin "13") (pinfunction "OUT_E_13") (pintype "passive"))
      (node (ref "D1") (pin "15") (pinfunction "OUT_E_15") (pintype "passive"))
      (node (ref "D1") (pin "9") (pinfunction "OUT_E_9") (pintype "passive"))
      (node (ref "JP1") (pin "2") (pinfunction "2_2") (pintype "passive"))
    )
    (net (code "180") (name "VCC_5V") (class "Default")
      (node (ref "C33") (pin "1") (pinfunction "1_1") (pintype "passive"))
      (node (ref "C34") (pin "2") (pinfunction "2_2") (pintype "passive"))
      (node (ref "JP11") (pin "5") (pinfunction "5_5") (pintype "passive"))
      (node (ref "JP11") (pin "7") (pinfunction "7_7") (pintype "passive"))
      (node (ref "U5") (pin "16") (pinfunction "VCC_16") (pintype "passive"))
      (node (ref "U6") (pin "3") (pinfunction "IN_3") (pintype "passive"))
      (node (ref "U7") (pin "4") (pinfunction "OUT_4") (pintype "passive"))
      (node (ref "USB1") (pin "1") (pinfunction "+5V_1") (pintype "passive"))
    )
    (net (code "181") (name "VCC_BLUE") (class "Default")
      (node (ref "C12") (pin "2") (pinfunction "2_2") (pintype "passive"))
      (node (ref "Q4") (pin "3") (pinfunction "D_3") (pintype "passive"))
      (node (ref "U3") (pin "12") (pinfunction "VCC_12") (pintype "passive"))
    )
    (net (code "182") (name "VCC_NB") (class "Default")
      (node (ref "C8") (pin "1") (pinfunction "1_1") (pintype "passive"))
      (node (ref "Q2") (pin "3") (pinfunction "D_3") (pintype "passive"))
      (node (ref "U1") (pin "45") (pinfunction "VBAT_45") (pintype "passive"))
      (node (ref "U1") (pin "46") (pinfunction "VBAT_46") (pintype "passive"))
    )
    (net (code "183") (name "unconnected-(U1A-ADC-Pad21)") (class "Default")
      (node (ref "U1") (pin "21") (pinfunction "ADC_21") (pintype "passive"))
    )
    (net (code "184") (name "unconnected-(U1A-DBG_RXD-Pad19)") (class "Default")
      (node (ref "U1") (pin "19") (pinfunction "DBG_RXD_19") (pintype "passive"))
    )
    (net (code "185") (name "unconnected-(U1A-DBG_TXD-Pad20)") (class "Default")
      (node (ref "U1") (pin "20") (pinfunction "DBG_TXD_20") (pintype "passive"))
    )
    (net (code "186") (name "unconnected-(U1A-NETLIGHT-Pad18)") (class "Default")
      (node (ref "U1") (pin "18") (pinfunction "NETLIGHT_18") (pintype "passive"))
    )
    (net (code "187") (name "unconnected-(U1A-RESERVED-Pad1)") (class "Default")
      (node (ref "U1") (pin "1") (pinfunction "RESERVED_1") (pintype "passive"))
    )
    (net (code "188") (name "unconnected-(U1A-RESERVED-Pad3)") (class "Default")
      (node (ref "U1") (pin "3") (pinfunction "RESERVED_3") (pintype "passive"))
    )
    (net (code "189") (name "unconnected-(U1A-RESERVED-Pad4)") (class "Default")
      (node (ref "U1") (pin "4") (pinfunction "RESERVED_4") (pintype "passive"))
    )
    (net (code "190") (name "unconnected-(U1A-RESERVED-Pad5)") (class "Default")
      (node (ref "U1") (pin "5") (pinfunction "RESERVED_5") (pintype "passive"))
    )
    (net (code "191") (name "unconnected-(U1A-RESERVED-Pad6)") (class "Default")
      (node (ref "U1") (pin "6") (pinfunction "RESERVED_6") (pintype "passive"))
    )
    (net (code "192") (name "unconnected-(U1A-RESERVED-Pad7)") (class "Default")
      (node (ref "U1") (pin "7") (pinfunction "RESERVED_7") (pintype "passive"))
    )
    (net (code "193") (name "unconnected-(U1A-RESERVED-Pad8)") (class "Default")
      (node (ref "U1") (pin "8") (pinfunction "RESERVED_8") (pintype "passive"))
    )
    (net (code "194") (name "unconnected-(U1A-RESERVED-Pad9)") (class "Default")
      (node (ref "U1") (pin "9") (pinfunction "RESERVED_9") (pintype "passive"))
    )
    (net (code "195") (name "unconnected-(U1A-RESERVED-Pad10)") (class "Default")
      (node (ref "U1") (pin "10") (pinfunction "RESERVED_10") (pintype "passive"))
    )
    (net (code "196") (name "unconnected-(U1A-RESERVED-Pad11)") (class "Default")
      (node (ref "U1") (pin "11") (pinfunction "RESERVED_11") (pintype "passive"))
    )
    (net (code "197") (name "unconnected-(U1A-RESERVED-Pad12)") (class "Default")
      (node (ref "U1") (pin "12") (pinfunction "RESERVED_12") (pintype "passive"))
    )
    (net (code "198") (name "unconnected-(U1A-RESERVED-Pad13)") (class "Default")
      (node (ref "U1") (pin "13") (pinfunction "RESERVED_13") (pintype "passive"))
    )
    (net (code "199") (name "unconnected-(U1A-RESERVED-Pad14)") (class "Default")
      (node (ref "U1") (pin "14") (pinfunction "RESERVED_14") (pintype "passive"))
    )
    (net (code "200") (name "unconnected-(U1A-RESERVED-Pad16)") (class "Default")
      (node (ref "U1") (pin "16") (pinfunction "RESERVED_16") (pintype "passive"))
    )
    (net (code "201") (name "unconnected-(U1A-RESERVED-Pad17)") (class "Default")
      (node (ref "U1") (pin "17") (pinfunction "RESERVED_17") (pintype "passive"))
    )
    (net (code "202") (name "unconnected-(U1A-RESERVED-Pad22)") (class "Default")
      (node (ref "U1") (pin "22") (pinfunction "RESERVED_22") (pintype "passive"))
    )
    (net (code "203") (name "unconnected-(U1A-RESERVED-Pad23)") (class "Default")
      (node (ref "U1") (pin "23") (pinfunction "RESERVED_23") (pintype "passive"))
    )
    (net (code "204") (name "unconnected-(U1A-RESERVED-Pad24)") (class "Default")
      (node (ref "U1") (pin "24") (pinfunction "RESERVED_24") (pintype "passive"))
    )
    (net (code "205") (name "unconnected-(U1A-RESERVED-Pad25)") (class "Default")
      (node (ref "U1") (pin "25") (pinfunction "RESERVED_25") (pintype "passive"))
    )
    (net (code "206") (name "unconnected-(U1A-RESERVED-Pad27)") (class "Default")
      (node (ref "U1") (pin "27") (pinfunction "RESERVED_27") (pintype "passive"))
    )
    (net (code "207") (name "unconnected-(U1A-RESERVED-Pad28)") (class "Default")
      (node (ref "U1") (pin "28") (pinfunction "RESERVED_28") (pintype "passive"))
    )
    (net (code "208") (name "unconnected-(U1A-RESERVED-Pad31)") (class "Default")
      (node (ref "U1") (pin "31") (pinfunction "RESERVED_31") (pintype "passive"))
    )
    (net (code "209") (name "unconnected-(U1A-RESERVED-Pad32)") (class "Default")
      (node (ref "U1") (pin "32") (pinfunction "RESERVED_32") (pintype "passive"))
    )
    (net (code "210") (name "unconnected-(U1A-RESERVED-Pad33)") (class "Default")
      (node (ref "U1") (pin "33") (pinfunction "RESERVED_33") (pintype "passive"))
    )
    (net (code "211") (name "unconnected-(U1A-RESERVED-Pad35)") (class "Default")
      (node (ref "U1") (pin "35") (pinfunction "RESERVED_35") (pintype "passive"))
    )
    (net (code "212") (name "unconnected-(U1A-RESERVED-Pad36)") (class "Default")
      (node (ref "U1") (pin "36") (pinfunction "RESERVED_36") (pintype "passive"))
    )
    (net (code "213") (name "unconnected-(U1A-RESERVED-Pad37)") (class "Default")
      (node (ref "U1") (pin "37") (pinfunction "RESERVED_37") (pintype "passive"))
    )
    (net (code "214") (name "unconnected-(U1A-RESERVED-Pad44)") (class "Default")
      (node (ref "U1") (pin "44") (pinfunction "RESERVED_44") (pintype "passive"))
    )
    (net (code "215") (name "unconnected-(U1A-RESERVED-Pad49)") (class "Default")
      (node (ref "U1") (pin "49") (pinfunction "RESERVED_49") (pintype "passive"))
    )
    (net (code "216") (name "unconnected-(U1A-RESERVED-Pad50)") (class "Default")
      (node (ref "U1") (pin "50") (pinfunction "RESERVED_50") (pintype "passive"))
    )
    (net (code "217") (name "unconnected-(U1A-RI-Pad34)") (class "Default")
      (node (ref "U1") (pin "34") (pinfunction "RI_34") (pintype "passive"))
    )
    (net (code "218") (name "unconnected-(U1A-VDD_EXT-Pad26)") (class "Default")
      (node (ref "U1") (pin "26") (pinfunction "VDD_EXT_26") (pintype "passive"))
    )
    (net (code "219") (name "unconnected-(U2-VPP-Pad5)") (class "Default")
      (node (ref "U2") (pin "5") (pinfunction "VPP_5") (pintype "passive"))
    )
    (net (code "220") (name "unconnected-(U3-DC-Pad6)") (class "Default")
      (node (ref "U3") (pin "6") (pinfunction "DC_6") (pintype "passive"))
    )
    (net (code "221") (name "unconnected-(U3-DD-Pad7)") (class "Default")
      (node (ref "U3") (pin "7") (pinfunction "DD_7") (pintype "passive"))
    )
    (net (code "222") (name "unconnected-(U3-GND-Pad28)") (class "Default")
      (node (ref "U3") (pin "28") (pinfunction "GND_28") (pintype "passive"))
    )
    (net (code "223") (name "unconnected-(U3-NC-Pad3)") (class "Default")
      (node (ref "U3") (pin "3") (pinfunction "NC_3") (pintype "passive"))
    )
    (net (code "224") (name "unconnected-(U3-NC-Pad4)") (class "Default")
      (node (ref "U3") (pin "4") (pinfunction "NC_4") (pintype "passive"))
    )
    (net (code "225") (name "unconnected-(U3-NC-Pad5)") (class "Default")
      (node (ref "U3") (pin "5") (pinfunction "NC_5") (pintype "passive"))
    )
    (net (code "226") (name "unconnected-(U3-P0.0-Pad26)") (class "Default")
      (node (ref "U3") (pin "26") (pinfunction "P0.0_26") (pintype "passive"))
    )
    (net (code "227") (name "unconnected-(U3-P0.1-Pad24)") (class "Default")
      (node (ref "U3") (pin "24") (pinfunction "P0.1_24") (pintype "passive"))
    )
    (net (code "228") (name "unconnected-(U3-P0.6-Pad23)") (class "Default")
      (node (ref "U3") (pin "23") (pinfunction "P0.6_23") (pintype "passive"))
    )
    (net (code "229") (name "unconnected-(U3-P0.7-Pad20)") (class "Default")
      (node (ref "U3") (pin "20") (pinfunction "P0.7_20") (pintype "passive"))
    )
    (net (code "230") (name "unconnected-(U3-P1.0-Pad19)") (class "Default")
      (node (ref "U3") (pin "19") (pinfunction "P1.0_19") (pintype "passive"))
    )
    (net (code "231") (name "unconnected-(U3-P1.4-Pad15)") (class "Default")
      (node (ref "U3") (pin "15") (pinfunction "P1.4_15") (pintype "passive"))
    )
    (net (code "232") (name "unconnected-(U3-P1.5-Pad25)") (class "Default")
      (node (ref "U3") (pin "25") (pinfunction "P1.5_25") (pintype "passive"))
    )
    (net (code "233") (name "unconnected-(U3-P1.6-Pad10)") (class "Default")
      (node (ref "U3") (pin "10") (pinfunction "P1.6_10") (pintype "passive"))
    )
    (net (code "234") (name "unconnected-(U3-P1.7-Pad9)") (class "Default")
      (node (ref "U3") (pin "9") (pinfunction "P1.7_9") (pintype "passive"))
    )
    (net (code "235") (name "unconnected-(U3-P2.0-Pad8)") (class "Default")
      (node (ref "U3") (pin "8") (pinfunction "P2.0_8") (pintype "passive"))
    )
    (net (code "236") (name "unconnected-(U3-RXD-Pad29)") (class "Default")
      (node (ref "U3") (pin "29") (pinfunction "RXD_29") (pintype "passive"))
    )
    (net (code "237") (name "unconnected-(U3-TXD-Pad30)") (class "Default")
      (node (ref "U3") (pin "30") (pinfunction "TXD_30") (pintype "passive"))
    )
    (net (code "238") (name "unconnected-(U3-USB_D+-Pad22)") (class "Default")
      (node (ref "U3") (pin "22") (pinfunction "USB_D+_22") (pintype "passive"))
    )
    (net (code "239") (name "unconnected-(U3-USB_D--Pad21)") (class "Default")
      (node (ref "U3") (pin "21") (pinfunction "USB_D-_21") (pintype "passive"))
    )
    (net (code "240") (name "unconnected-(U3-VCC-Pad27)") (class "Default")
      (node (ref "U3") (pin "27") (pinfunction "VCC_27") (pintype "passive"))
    )
    (net (code "241") (name "unconnected-(U4-NC-Pad106)") (class "Default")
      (node (ref "U4") (pin "106") (pinfunction "NC_106") (pintype "passive"))
    )
    (net (code "242") (name "unconnected-(U4-PA11{slash}USART1_CTS{slash}CAN_RX{slash}TIM1_CH4{slash}USBDM-Pad103)") (class "Default")
      (node (ref "U4") (pin "103") (pinfunction "PA11/USART1_CTS/CAN_RX/TIM1_CH4/USBDM_103") (pintype "passive"))
    )
    (net (code "243") (name "unconnected-(U4-PA12{slash}USART1_RTS{slash}CAN_TX{slash}TIM1_ETR{slash}USBDP-Pad104)") (class "Default")
      (node (ref "U4") (pin "104") (pinfunction "PA12/USART1_RTS/CAN_TX/TIM1_ETR/USBDP_104") (pintype "passive"))
    )
    (net (code "244") (name "unconnected-(U4-PB0{slash}ADC12_IN8{slash}TIM3_CH3{slash}TIM8_CH2N-Pad46)") (class "Default")
      (node (ref "U4") (pin "46") (pinfunction "PB0/ADC12_IN8/TIM3_CH3/TIM8_CH2N_46") (pintype "passive"))
    )
    (net (code "245") (name "unconnected-(U4-PB1{slash}ADC12_IN9{slash}TIM3_CH4{slash}TIM8_CH3N-Pad47)") (class "Default")
      (node (ref "U4") (pin "47") (pinfunction "PB1/ADC12_IN9/TIM3_CH4/TIM8_CH3N_47") (pintype "passive"))
    )
    (net (code "246") (name "unconnected-(U4-VDD-Pad17)") (class "Default")
      (node (ref "U4") (pin "17") (pinfunction "VDD_17") (pintype "passive"))
    )
    (net (code "247") (name "unconnected-(U4-VDD-Pad52)") (class "Default")
      (node (ref "U4") (pin "52") (pinfunction "VDD_52") (pintype "passive"))
    )
    (net (code "248") (name "unconnected-(U4-VDD-Pad62)") (class "Default")
      (node (ref "U4") (pin "62") (pinfunction "VDD_62") (pintype "passive"))
    )
    (net (code "249") (name "unconnected-(U4-VDD-Pad84)") (class "Default")
      (node (ref "U4") (pin "84") (pinfunction "VDD_84") (pintype "passive"))
    )
    (net (code "250") (name "unconnected-(U4-VDD-Pad95)") (class "Default")
      (node (ref "U4") (pin "95") (pinfunction "VDD_95") (pintype "passive"))
    )
    (net (code "251") (name "unconnected-(U4-VDD-Pad121)") (class "Default")
      (node (ref "U4") (pin "121") (pinfunction "VDD_121") (pintype "passive"))
    )
    (net (code "252") (name "unconnected-(U4-VDD-Pad131)") (class "Default")
      (node (ref "U4") (pin "131") (pinfunction "VDD_131") (pintype "passive"))
    )
    (net (code "253") (name "unconnected-(U4-VSS-Pad16)") (class "Default")
      (node (ref "U4") (pin "16") (pinfunction "VSS_16") (pintype "passive"))
    )
    (net (code "254") (name "unconnected-(U4-VSS-Pad51)") (class "Default")
      (node (ref "U4") (pin "51") (pinfunction "VSS_51") (pintype "passive"))
    )
    (net (code "255") (name "unconnected-(U4-VSS-Pad61)") (class "Default")
      (node (ref "U4") (pin "61") (pinfunction "VSS_61") (pintype "passive"))
    )
    (net (code "256") (name "unconnected-(U4-VSS-Pad83)") (class "Default")
      (node (ref "U4") (pin "83") (pinfunction "VSS_83") (pintype "passive"))
    )
    (net (code "257") (name "unconnected-(U4-VSS-Pad94)") (class "Default")
      (node (ref "U4") (pin "94") (pinfunction "VSS_94") (pintype "passive"))
    )
    (net (code "258") (name "unconnected-(U4-VSS-Pad120)") (class "Default")
      (node (ref "U4") (pin "120") (pinfunction "VSS_120") (pintype "passive"))
    )
    (net (code "259") (name "unconnected-(U4-VSS-Pad130)") (class "Default")
      (node (ref "U4") (pin "130") (pinfunction "VSS_130") (pintype "passive"))
    )
    (net (code "260") (name "unconnected-(U5-CTS-Pad9)") (class "Default")
      (node (ref "U5") (pin "9") (pinfunction "CTS_9") (pintype "passive"))
    )
    (net (code "261") (name "unconnected-(U5-DSR-Pad10)") (class "Default")
      (node (ref "U5") (pin "10") (pinfunction "DSR_10") (pintype "passive"))
    )
    (net (code "262") (name "unconnected-(U5-DTR-Pad13)") (class "Default")
      (node (ref "U5") (pin "13") (pinfunction "DTR_13") (pintype "passive"))
    )
    (net (code "263") (name "unconnected-(U5-R233-Pad15)") (class "Default")
      (node (ref "U5") (pin "15") (pinfunction "R233_15") (pintype "passive"))
    )
    (net (code "264") (name "unconnected-(U5-RCD-Pad12)") (class "Default")
      (node (ref "U5") (pin "12") (pinfunction "RCD_12") (pintype "passive"))
    )
    (net (code "265") (name "unconnected-(U5-RI-Pad11)") (class "Default")
      (node (ref "U5") (pin "11") (pinfunction "RI_11") (pintype "passive"))
    )
    (net (code "266") (name "unconnected-(U5-RTS-Pad14)") (class "Default")
      (node (ref "U5") (pin "14") (pinfunction "RTS_14") (pintype "passive"))
    )
    (net (code "267") (name "unconnected-(U5-XD-Pad8)") (class "Default")
      (node (ref "U5") (pin "8") (pinfunction "XD_8") (pintype "passive"))
    )
    (net (code "268") (name "unconnected-(U5-XI-Pad7)") (class "Default")
      (node (ref "U5") (pin "7") (pinfunction "XI_7") (pintype "passive"))
    )
    (net (code "269") (name "unconnected-(U7-OUT-Pad2)") (class "Default")
      (node (ref "U7") (pin "2") (pinfunction "OUT_2") (pintype "passive"))
    )
    (net (code "270") (name "unconnected-(X2-Pad2)") (class "Default")
      (node (ref "X2") (pin "2") (pinfunction "2_2") (pintype "passive"))
    )
    (net (code "271") (name "unconnected-(X2-Pad4)") (class "Default")
      (node (ref "X2") (pin "4") (pinfunction "4_4") (pintype "passive"))
    )
  )
)
